# SCH_MD001_2022-09-17.net
KiCad netlist of a schematic drawn in EasyEDA
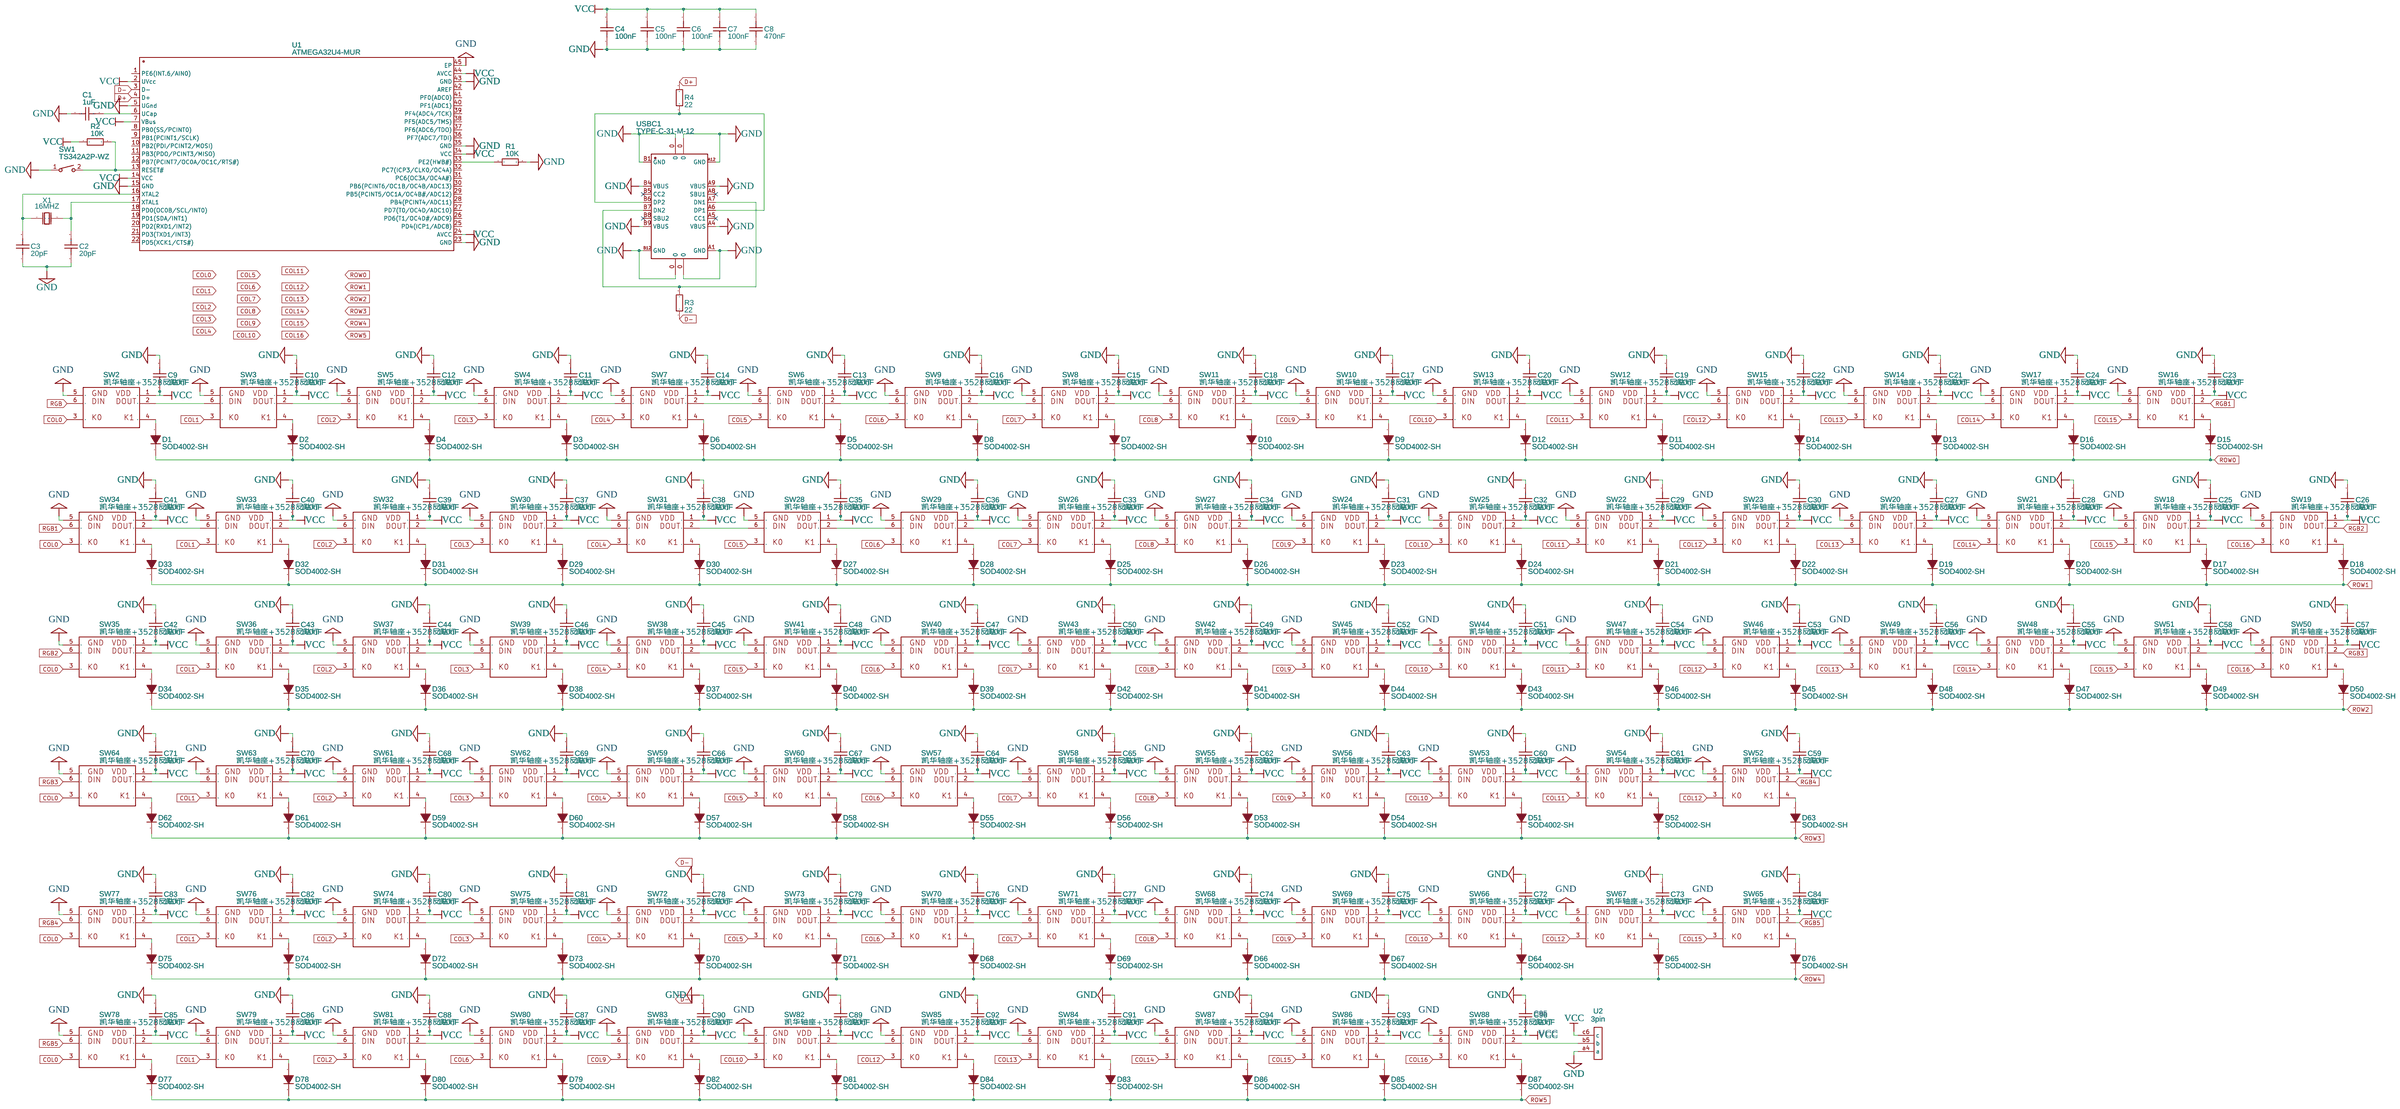
[diagram p0: schematic sheet]

(export (version "E")
  (design (tool "Eeschema 10.0.6"))
  (components
    (comp (ref "C1")
      (value "1uF")
      (fields
        (field (name "BOM_Manufacturer Part") "TCC0805X7R105K250DTS")
        (field (name "BOM_Supplier Part") "C344171")
      )
      (libsource (lib "") (part "TCC0805X7R105K250DTS"))
    )
    (comp (ref "C2")
      (value "20pF")
      (fields
        (field (name "BOM_Manufacturer Part") "VJ0805D200KXPAP")
        (field (name "BOM_Supplier Part") "C2309612")
      )
      (libsource (lib "") (part "VJ0805D200KXPAP"))
    )
    (comp (ref "C3")
      (value "20pF")
      (fields
        (field (name "BOM_Manufacturer Part") "VJ0805D200KXPAP")
        (field (name "BOM_Supplier Part") "C2309612")
      )
      (libsource (lib "") (part "VJ0805D200KXPAP"))
    )
    (comp (ref "C4")
      (value "100nF")
      (fields
        (field (name "BOM_Manufacturer Part") "VJ0805Y104MXXMG")
        (field (name "BOM_Supplier Part") "C2234470")
      )
      (libsource (lib "") (part "VJ0805Y104MXXMG"))
    )
    (comp (ref "C5")
      (value "100nF")
      (fields
        (field (name "BOM_Manufacturer Part") "VJ0805Y104MXXMG")
        (field (name "BOM_Supplier Part") "C2234470")
      )
      (libsource (lib "") (part "VJ0805Y104MXXMG"))
    )
    (comp (ref "C6")
      (value "100nF")
      (fields
        (field (name "BOM_Manufacturer Part") "VJ0805Y104MXXMG")
        (field (name "BOM_Supplier Part") "C2234470")
      )
      (libsource (lib "") (part "VJ0805Y104MXXMG"))
    )
    (comp (ref "C7")
      (value "100nF")
      (fields
        (field (name "BOM_Manufacturer Part") "VJ0805Y104MXXMG")
        (field (name "BOM_Supplier Part") "C2234470")
      )
      (libsource (lib "") (part "VJ0805Y104MXXMG"))
    )
    (comp (ref "C8")
      (value "470nF")
      (fields
        (field (name "BOM_Manufacturer Part") "TCC0805Y5V474M500DT")
        (field (name "BOM_Supplier Part") "C377012")
      )
      (libsource (lib "") (part "TCC0805Y5V474M500DT"))
    )
    (comp (ref "C9")
      (value "100nF")
      (fields
        (field (name "BOM_Manufacturer Part") "VJ0805Y104MXXMG")
        (field (name "BOM_Supplier Part") "C2234470")
      )
      (libsource (lib "") (part "VJ0805Y104MXXMG"))
    )
    (comp (ref "C10")
      (value "100nF")
      (fields
        (field (name "BOM_Manufacturer Part") "VJ0805Y104MXXMG")
        (field (name "BOM_Supplier Part") "C2234470")
      )
      (libsource (lib "") (part "VJ0805Y104MXXMG"))
    )
    (comp (ref "C11")
      (value "100nF")
      (fields
        (field (name "BOM_Manufacturer Part") "VJ0805Y104MXXMG")
        (field (name "BOM_Supplier Part") "C2234470")
      )
      (libsource (lib "") (part "VJ0805Y104MXXMG"))
    )
    (comp (ref "C12")
      (value "100nF")
      (fields
        (field (name "BOM_Manufacturer Part") "VJ0805Y104MXXMG")
        (field (name "BOM_Supplier Part") "C2234470")
      )
      (libsource (lib "") (part "VJ0805Y104MXXMG"))
    )
    (comp (ref "C13")
      (value "100nF")
      (fields
        (field (name "BOM_Manufacturer Part") "VJ0805Y104MXXMG")
        (field (name "BOM_Supplier Part") "C2234470")
      )
      (libsource (lib "") (part "VJ0805Y104MXXMG"))
    )
    (comp (ref "C14")
      (value "100nF")
      (fields
        (field (name "BOM_Manufacturer Part") "VJ0805Y104MXXMG")
        (field (name "BOM_Supplier Part") "C2234470")
      )
      (libsource (lib "") (part "VJ0805Y104MXXMG"))
    )
    (comp (ref "C15")
      (value "100nF")
      (fields
        (field (name "BOM_Manufacturer Part") "VJ0805Y104MXXMG")
        (field (name "BOM_Supplier Part") "C2234470")
      )
      (libsource (lib "") (part "VJ0805Y104MXXMG"))
    )
    (comp (ref "C16")
      (value "100nF")
      (fields
        (field (name "BOM_Manufacturer Part") "VJ0805Y104MXXMG")
        (field (name "BOM_Supplier Part") "C2234470")
      )
      (libsource (lib "") (part "VJ0805Y104MXXMG"))
    )
    (comp (ref "C17")
      (value "100nF")
      (fields
        (field (name "BOM_Manufacturer Part") "VJ0805Y104MXXMG")
        (field (name "BOM_Supplier Part") "C2234470")
      )
      (libsource (lib "") (part "VJ0805Y104MXXMG"))
    )
    (comp (ref "C18")
      (value "100nF")
      (fields
        (field (name "BOM_Manufacturer Part") "VJ0805Y104MXXMG")
        (field (name "BOM_Supplier Part") "C2234470")
      )
      (libsource (lib "") (part "VJ0805Y104MXXMG"))
    )
    (comp (ref "C19")
      (value "100nF")
      (fields
        (field (name "BOM_Manufacturer Part") "VJ0805Y104MXXMG")
        (field (name "BOM_Supplier Part") "C2234470")
      )
      (libsource (lib "") (part "VJ0805Y104MXXMG"))
    )
    (comp (ref "C20")
      (value "100nF")
      (fields
        (field (name "BOM_Manufacturer Part") "VJ0805Y104MXXMG")
        (field (name "BOM_Supplier Part") "C2234470")
      )
      (libsource (lib "") (part "VJ0805Y104MXXMG"))
    )
    (comp (ref "C21")
      (value "100nF")
      (fields
        (field (name "BOM_Manufacturer Part") "VJ0805Y104MXXMG")
        (field (name "BOM_Supplier Part") "C2234470")
      )
      (libsource (lib "") (part "VJ0805Y104MXXMG"))
    )
    (comp (ref "C22")
      (value "100nF")
      (fields
        (field (name "BOM_Manufacturer Part") "VJ0805Y104MXXMG")
        (field (name "BOM_Supplier Part") "C2234470")
      )
      (libsource (lib "") (part "VJ0805Y104MXXMG"))
    )
    (comp (ref "C23")
      (value "100nF")
      (fields
        (field (name "BOM_Manufacturer Part") "VJ0805Y104MXXMG")
        (field (name "BOM_Supplier Part") "C2234470")
      )
      (libsource (lib "") (part "VJ0805Y104MXXMG"))
    )
    (comp (ref "C24")
      (value "100nF")
      (fields
        (field (name "BOM_Manufacturer Part") "VJ0805Y104MXXMG")
        (field (name "BOM_Supplier Part") "C2234470")
      )
      (libsource (lib "") (part "VJ0805Y104MXXMG"))
    )
    (comp (ref "C25")
      (value "100nF")
      (fields
        (field (name "BOM_Manufacturer Part") "VJ0805Y104MXXMG")
        (field (name "BOM_Supplier Part") "C2234470")
      )
      (libsource (lib "") (part "VJ0805Y104MXXMG"))
    )
    (comp (ref "C26")
      (value "100nF")
      (fields
        (field (name "BOM_Manufacturer Part") "VJ0805Y104MXXMG")
        (field (name "BOM_Supplier Part") "C2234470")
      )
      (libsource (lib "") (part "VJ0805Y104MXXMG"))
    )
    (comp (ref "C27")
      (value "100nF")
      (fields
        (field (name "BOM_Manufacturer Part") "VJ0805Y104MXXMG")
        (field (name "BOM_Supplier Part") "C2234470")
      )
      (libsource (lib "") (part "VJ0805Y104MXXMG"))
    )
    (comp (ref "C28")
      (value "100nF")
      (fields
        (field (name "BOM_Manufacturer Part") "VJ0805Y104MXXMG")
        (field (name "BOM_Supplier Part") "C2234470")
      )
      (libsource (lib "") (part "VJ0805Y104MXXMG"))
    )
    (comp (ref "C29")
      (value "100nF")
      (fields
        (field (name "BOM_Manufacturer Part") "VJ0805Y104MXXMG")
        (field (name "BOM_Supplier Part") "C2234470")
      )
      (libsource (lib "") (part "VJ0805Y104MXXMG"))
    )
    (comp (ref "C30")
      (value "100nF")
      (fields
        (field (name "BOM_Manufacturer Part") "VJ0805Y104MXXMG")
        (field (name "BOM_Supplier Part") "C2234470")
      )
      (libsource (lib "") (part "VJ0805Y104MXXMG"))
    )
    (comp (ref "C31")
      (value "100nF")
      (fields
        (field (name "BOM_Manufacturer Part") "VJ0805Y104MXXMG")
        (field (name "BOM_Supplier Part") "C2234470")
      )
      (libsource (lib "") (part "VJ0805Y104MXXMG"))
    )
    (comp (ref "C32")
      (value "100nF")
      (fields
        (field (name "BOM_Manufacturer Part") "VJ0805Y104MXXMG")
        (field (name "BOM_Supplier Part") "C2234470")
      )
      (libsource (lib "") (part "VJ0805Y104MXXMG"))
    )
    (comp (ref "C33")
      (value "100nF")
      (fields
        (field (name "BOM_Manufacturer Part") "VJ0805Y104MXXMG")
        (field (name "BOM_Supplier Part") "C2234470")
      )
      (libsource (lib "") (part "VJ0805Y104MXXMG"))
    )
    (comp (ref "C34")
      (value "100nF")
      (fields
        (field (name "BOM_Manufacturer Part") "VJ0805Y104MXXMG")
        (field (name "BOM_Supplier Part") "C2234470")
      )
      (libsource (lib "") (part "VJ0805Y104MXXMG"))
    )
    (comp (ref "C35")
      (value "100nF")
      (fields
        (field (name "BOM_Manufacturer Part") "VJ0805Y104MXXMG")
        (field (name "BOM_Supplier Part") "C2234470")
      )
      (libsource (lib "") (part "VJ0805Y104MXXMG"))
    )
    (comp (ref "C36")
      (value "100nF")
      (fields
        (field (name "BOM_Manufacturer Part") "VJ0805Y104MXXMG")
        (field (name "BOM_Supplier Part") "C2234470")
      )
      (libsource (lib "") (part "VJ0805Y104MXXMG"))
    )
    (comp (ref "C37")
      (value "100nF")
      (fields
        (field (name "BOM_Manufacturer Part") "VJ0805Y104MXXMG")
        (field (name "BOM_Supplier Part") "C2234470")
      )
      (libsource (lib "") (part "VJ0805Y104MXXMG"))
    )
    (comp (ref "C38")
      (value "100nF")
      (fields
        (field (name "BOM_Manufacturer Part") "VJ0805Y104MXXMG")
        (field (name "BOM_Supplier Part") "C2234470")
      )
      (libsource (lib "") (part "VJ0805Y104MXXMG"))
    )
    (comp (ref "C39")
      (value "100nF")
      (fields
        (field (name "BOM_Manufacturer Part") "VJ0805Y104MXXMG")
        (field (name "BOM_Supplier Part") "C2234470")
      )
      (libsource (lib "") (part "VJ0805Y104MXXMG"))
    )
    (comp (ref "C40")
      (value "100nF")
      (fields
        (field (name "BOM_Manufacturer Part") "VJ0805Y104MXXMG")
        (field (name "BOM_Supplier Part") "C2234470")
      )
      (libsource (lib "") (part "VJ0805Y104MXXMG"))
    )
    (comp (ref "C41")
      (value "100nF")
      (fields
        (field (name "BOM_Manufacturer Part") "VJ0805Y104MXXMG")
        (field (name "BOM_Supplier Part") "C2234470")
      )
      (libsource (lib "") (part "VJ0805Y104MXXMG"))
    )
    (comp (ref "C42")
      (value "100nF")
      (fields
        (field (name "BOM_Manufacturer Part") "VJ0805Y104MXXMG")
        (field (name "BOM_Supplier Part") "C2234470")
      )
      (libsource (lib "") (part "VJ0805Y104MXXMG"))
    )
    (comp (ref "C43")
      (value "100nF")
      (fields
        (field (name "BOM_Manufacturer Part") "VJ0805Y104MXXMG")
        (field (name "BOM_Supplier Part") "C2234470")
      )
      (libsource (lib "") (part "VJ0805Y104MXXMG"))
    )
    (comp (ref "C44")
      (value "100nF")
      (fields
        (field (name "BOM_Manufacturer Part") "VJ0805Y104MXXMG")
        (field (name "BOM_Supplier Part") "C2234470")
      )
      (libsource (lib "") (part "VJ0805Y104MXXMG"))
    )
    (comp (ref "C45")
      (value "100nF")
      (fields
        (field (name "BOM_Manufacturer Part") "VJ0805Y104MXXMG")
        (field (name "BOM_Supplier Part") "C2234470")
      )
      (libsource (lib "") (part "VJ0805Y104MXXMG"))
    )
    (comp (ref "C46")
      (value "100nF")
      (fields
        (field (name "BOM_Manufacturer Part") "VJ0805Y104MXXMG")
        (field (name "BOM_Supplier Part") "C2234470")
      )
      (libsource (lib "") (part "VJ0805Y104MXXMG"))
    )
    (comp (ref "C47")
      (value "100nF")
      (fields
        (field (name "BOM_Manufacturer Part") "VJ0805Y104MXXMG")
        (field (name "BOM_Supplier Part") "C2234470")
      )
      (libsource (lib "") (part "VJ0805Y104MXXMG"))
    )
    (comp (ref "C48")
      (value "100nF")
      (fields
        (field (name "BOM_Manufacturer Part") "VJ0805Y104MXXMG")
        (field (name "BOM_Supplier Part") "C2234470")
      )
      (libsource (lib "") (part "VJ0805Y104MXXMG"))
    )
    (comp (ref "C49")
      (value "100nF")
      (fields
        (field (name "BOM_Manufacturer Part") "VJ0805Y104MXXMG")
        (field (name "BOM_Supplier Part") "C2234470")
      )
      (libsource (lib "") (part "VJ0805Y104MXXMG"))
    )
    (comp (ref "C50")
      (value "100nF")
      (fields
        (field (name "BOM_Manufacturer Part") "VJ0805Y104MXXMG")
        (field (name "BOM_Supplier Part") "C2234470")
      )
      (libsource (lib "") (part "VJ0805Y104MXXMG"))
    )
    (comp (ref "C51")
      (value "100nF")
      (fields
        (field (name "BOM_Manufacturer Part") "VJ0805Y104MXXMG")
        (field (name "BOM_Supplier Part") "C2234470")
      )
      (libsource (lib "") (part "VJ0805Y104MXXMG"))
    )
    (comp (ref "C52")
      (value "100nF")
      (fields
        (field (name "BOM_Manufacturer Part") "VJ0805Y104MXXMG")
        (field (name "BOM_Supplier Part") "C2234470")
      )
      (libsource (lib "") (part "VJ0805Y104MXXMG"))
    )
    (comp (ref "C53")
      (value "100nF")
      (fields
        (field (name "BOM_Manufacturer Part") "VJ0805Y104MXXMG")
        (field (name "BOM_Supplier Part") "C2234470")
      )
      (libsource (lib "") (part "VJ0805Y104MXXMG"))
    )
    (comp (ref "C54")
      (value "100nF")
      (fields
        (field (name "BOM_Manufacturer Part") "VJ0805Y104MXXMG")
        (field (name "BOM_Supplier Part") "C2234470")
      )
      (libsource (lib "") (part "VJ0805Y104MXXMG"))
    )
    (comp (ref "C55")
      (value "100nF")
      (fields
        (field (name "BOM_Manufacturer Part") "VJ0805Y104MXXMG")
        (field (name "BOM_Supplier Part") "C2234470")
      )
      (libsource (lib "") (part "VJ0805Y104MXXMG"))
    )
    (comp (ref "C56")
      (value "100nF")
      (fields
        (field (name "BOM_Manufacturer Part") "VJ0805Y104MXXMG")
        (field (name "BOM_Supplier Part") "C2234470")
      )
      (libsource (lib "") (part "VJ0805Y104MXXMG"))
    )
    (comp (ref "C57")
      (value "100nF")
      (fields
        (field (name "BOM_Manufacturer Part") "VJ0805Y104MXXMG")
        (field (name "BOM_Supplier Part") "C2234470")
      )
      (libsource (lib "") (part "VJ0805Y104MXXMG"))
    )
    (comp (ref "C58")
      (value "100nF")
      (fields
        (field (name "BOM_Manufacturer Part") "VJ0805Y104MXXMG")
        (field (name "BOM_Supplier Part") "C2234470")
      )
      (libsource (lib "") (part "VJ0805Y104MXXMG"))
    )
    (comp (ref "C59")
      (value "100nF")
      (fields
        (field (name "BOM_Manufacturer Part") "VJ0805Y104MXXMG")
        (field (name "BOM_Supplier Part") "C2234470")
      )
      (libsource (lib "") (part "VJ0805Y104MXXMG"))
    )
    (comp (ref "C60")
      (value "100nF")
      (fields
        (field (name "BOM_Manufacturer Part") "VJ0805Y104MXXMG")
        (field (name "BOM_Supplier Part") "C2234470")
      )
      (libsource (lib "") (part "VJ0805Y104MXXMG"))
    )
    (comp (ref "C61")
      (value "100nF")
      (fields
        (field (name "BOM_Manufacturer Part") "VJ0805Y104MXXMG")
        (field (name "BOM_Supplier Part") "C2234470")
      )
      (libsource (lib "") (part "VJ0805Y104MXXMG"))
    )
    (comp (ref "C62")
      (value "100nF")
      (fields
        (field (name "BOM_Manufacturer Part") "VJ0805Y104MXXMG")
        (field (name "BOM_Supplier Part") "C2234470")
      )
      (libsource (lib "") (part "VJ0805Y104MXXMG"))
    )
    (comp (ref "C63")
      (value "100nF")
      (fields
        (field (name "BOM_Manufacturer Part") "VJ0805Y104MXXMG")
        (field (name "BOM_Supplier Part") "C2234470")
      )
      (libsource (lib "") (part "VJ0805Y104MXXMG"))
    )
    (comp (ref "C64")
      (value "100nF")
      (fields
        (field (name "BOM_Manufacturer Part") "VJ0805Y104MXXMG")
        (field (name "BOM_Supplier Part") "C2234470")
      )
      (libsource (lib "") (part "VJ0805Y104MXXMG"))
    )
    (comp (ref "C65")
      (value "100nF")
      (fields
        (field (name "BOM_Manufacturer Part") "VJ0805Y104MXXMG")
        (field (name "BOM_Supplier Part") "C2234470")
      )
      (libsource (lib "") (part "VJ0805Y104MXXMG"))
    )
    (comp (ref "C66")
      (value "100nF")
      (fields
        (field (name "BOM_Manufacturer Part") "VJ0805Y104MXXMG")
        (field (name "BOM_Supplier Part") "C2234470")
      )
      (libsource (lib "") (part "VJ0805Y104MXXMG"))
    )
    (comp (ref "C67")
      (value "100nF")
      (fields
        (field (name "BOM_Manufacturer Part") "VJ0805Y104MXXMG")
        (field (name "BOM_Supplier Part") "C2234470")
      )
      (libsource (lib "") (part "VJ0805Y104MXXMG"))
    )
    (comp (ref "C68")
      (value "100nF")
      (fields
        (field (name "BOM_Manufacturer Part") "VJ0805Y104MXXMG")
        (field (name "BOM_Supplier Part") "C2234470")
      )
      (libsource (lib "") (part "VJ0805Y104MXXMG"))
    )
    (comp (ref "C69")
      (value "100nF")
      (fields
        (field (name "BOM_Manufacturer Part") "VJ0805Y104MXXMG")
        (field (name "BOM_Supplier Part") "C2234470")
      )
      (libsource (lib "") (part "VJ0805Y104MXXMG"))
    )
    (comp (ref "C70")
      (value "100nF")
      (fields
        (field (name "BOM_Manufacturer Part") "VJ0805Y104MXXMG")
        (field (name "BOM_Supplier Part") "C2234470")
      )
      (libsource (lib "") (part "VJ0805Y104MXXMG"))
    )
    (comp (ref "C71")
      (value "100nF")
      (fields
        (field (name "BOM_Manufacturer Part") "VJ0805Y104MXXMG")
        (field (name "BOM_Supplier Part") "C2234470")
      )
      (libsource (lib "") (part "VJ0805Y104MXXMG"))
    )
    (comp (ref "C72")
      (value "100nF")
      (fields
        (field (name "BOM_Manufacturer Part") "VJ0805Y104MXXMG")
        (field (name "BOM_Supplier Part") "C2234470")
      )
      (libsource (lib "") (part "VJ0805Y104MXXMG"))
    )
    (comp (ref "C73")
      (value "100nF")
      (fields
        (field (name "BOM_Manufacturer Part") "VJ0805Y104MXXMG")
        (field (name "BOM_Supplier Part") "C2234470")
      )
      (libsource (lib "") (part "VJ0805Y104MXXMG"))
    )
    (comp (ref "C74")
      (value "100nF")
      (fields
        (field (name "BOM_Manufacturer Part") "VJ0805Y104MXXMG")
        (field (name "BOM_Supplier Part") "C2234470")
      )
      (libsource (lib "") (part "VJ0805Y104MXXMG"))
    )
    (comp (ref "C75")
      (value "100nF")
      (fields
        (field (name "BOM_Manufacturer Part") "VJ0805Y104MXXMG")
        (field (name "BOM_Supplier Part") "C2234470")
      )
      (libsource (lib "") (part "VJ0805Y104MXXMG"))
    )
    (comp (ref "C76")
      (value "100nF")
      (fields
        (field (name "BOM_Manufacturer Part") "VJ0805Y104MXXMG")
        (field (name "BOM_Supplier Part") "C2234470")
      )
      (libsource (lib "") (part "VJ0805Y104MXXMG"))
    )
    (comp (ref "C77")
      (value "100nF")
      (fields
        (field (name "BOM_Manufacturer Part") "VJ0805Y104MXXMG")
        (field (name "BOM_Supplier Part") "C2234470")
      )
      (libsource (lib "") (part "VJ0805Y104MXXMG"))
    )
    (comp (ref "C78")
      (value "100nF")
      (fields
        (field (name "BOM_Manufacturer Part") "VJ0805Y104MXXMG")
        (field (name "BOM_Supplier Part") "C2234470")
      )
      (libsource (lib "") (part "VJ0805Y104MXXMG"))
    )
    (comp (ref "C79")
      (value "100nF")
      (fields
        (field (name "BOM_Manufacturer Part") "VJ0805Y104MXXMG")
        (field (name "BOM_Supplier Part") "C2234470")
      )
      (libsource (lib "") (part "VJ0805Y104MXXMG"))
    )
    (comp (ref "C80")
      (value "100nF")
      (fields
        (field (name "BOM_Manufacturer Part") "VJ0805Y104MXXMG")
        (field (name "BOM_Supplier Part") "C2234470")
      )
      (libsource (lib "") (part "VJ0805Y104MXXMG"))
    )
    (comp (ref "C81")
      (value "100nF")
      (fields
        (field (name "BOM_Manufacturer Part") "VJ0805Y104MXXMG")
        (field (name "BOM_Supplier Part") "C2234470")
      )
      (libsource (lib "") (part "VJ0805Y104MXXMG"))
    )
    (comp (ref "C82")
      (value "100nF")
      (fields
        (field (name "BOM_Manufacturer Part") "VJ0805Y104MXXMG")
        (field (name "BOM_Supplier Part") "C2234470")
      )
      (libsource (lib "") (part "VJ0805Y104MXXMG"))
    )
    (comp (ref "C83")
      (value "100nF")
      (fields
        (field (name "BOM_Manufacturer Part") "VJ0805Y104MXXMG")
        (field (name "BOM_Supplier Part") "C2234470")
      )
      (libsource (lib "") (part "VJ0805Y104MXXMG"))
    )
    (comp (ref "C84")
      (value "100nF")
      (fields
        (field (name "BOM_Manufacturer Part") "VJ0805Y104MXXMG")
        (field (name "BOM_Supplier Part") "C2234470")
      )
      (libsource (lib "") (part "VJ0805Y104MXXMG"))
    )
    (comp (ref "C85")
      (value "100nF")
      (fields
        (field (name "BOM_Manufacturer Part") "VJ0805Y104MXXMG")
        (field (name "BOM_Supplier Part") "C2234470")
      )
      (libsource (lib "") (part "VJ0805Y104MXXMG"))
    )
    (comp (ref "C86")
      (value "100nF")
      (fields
        (field (name "BOM_Manufacturer Part") "VJ0805Y104MXXMG")
        (field (name "BOM_Supplier Part") "C2234470")
      )
      (libsource (lib "") (part "VJ0805Y104MXXMG"))
    )
    (comp (ref "C87")
      (value "100nF")
      (fields
        (field (name "BOM_Manufacturer Part") "VJ0805Y104MXXMG")
        (field (name "BOM_Supplier Part") "C2234470")
      )
      (libsource (lib "") (part "VJ0805Y104MXXMG"))
    )
    (comp (ref "C88")
      (value "100nF")
      (fields
        (field (name "BOM_Manufacturer Part") "VJ0805Y104MXXMG")
        (field (name "BOM_Supplier Part") "C2234470")
      )
      (libsource (lib "") (part "VJ0805Y104MXXMG"))
    )
    (comp (ref "C89")
      (value "100nF")
      (fields
        (field (name "BOM_Manufacturer Part") "VJ0805Y104MXXMG")
        (field (name "BOM_Supplier Part") "C2234470")
      )
      (libsource (lib "") (part "VJ0805Y104MXXMG"))
    )
    (comp (ref "C90")
      (value "100nF")
      (fields
        (field (name "BOM_Manufacturer Part") "VJ0805Y104MXXMG")
        (field (name "BOM_Supplier Part") "C2234470")
      )
      (libsource (lib "") (part "VJ0805Y104MXXMG"))
    )
    (comp (ref "C91")
      (value "100nF")
      (fields
        (field (name "BOM_Manufacturer Part") "VJ0805Y104MXXMG")
        (field (name "BOM_Supplier Part") "C2234470")
      )
      (libsource (lib "") (part "VJ0805Y104MXXMG"))
    )
    (comp (ref "C92")
      (value "100nF")
      (fields
        (field (name "BOM_Manufacturer Part") "VJ0805Y104MXXMG")
        (field (name "BOM_Supplier Part") "C2234470")
      )
      (libsource (lib "") (part "VJ0805Y104MXXMG"))
    )
    (comp (ref "C93")
      (value "100nF")
      (fields
        (field (name "BOM_Manufacturer Part") "VJ0805Y104MXXMG")
        (field (name "BOM_Supplier Part") "C2234470")
      )
      (libsource (lib "") (part "VJ0805Y104MXXMG"))
    )
    (comp (ref "C94")
      (value "100nF")
      (fields
        (field (name "BOM_Manufacturer Part") "VJ0805Y104MXXMG")
        (field (name "BOM_Supplier Part") "C2234470")
      )
      (libsource (lib "") (part "VJ0805Y104MXXMG"))
    )
    (comp (ref "C96")
      (value "100nF")
      (fields
        (field (name "BOM_Manufacturer Part") "VJ0805Y104MXXMG")
        (field (name "BOM_Supplier Part") "C2234470")
      )
      (libsource (lib "") (part "VJ0805Y104MXXMG"))
    )
    (comp (ref "D1")
      (value "SOD4002-SH")
      (fields (field (name "BOM_Supplier Part") "C154996"))
      (libsource (lib "") (part "SOD4002-SH_1"))
    )
    (comp (ref "D2")
      (value "SOD4002-SH")
      (fields (field (name "BOM_Supplier Part") "C154996"))
      (libsource (lib "") (part "SOD4002-SH_1"))
    )
    (comp (ref "D3")
      (value "SOD4002-SH")
      (fields (field (name "BOM_Supplier Part") "C154996"))
      (libsource (lib "") (part "SOD4002-SH_1"))
    )
    (comp (ref "D4")
      (value "SOD4002-SH")
      (fields (field (name "BOM_Supplier Part") "C154996"))
      (libsource (lib "") (part "SOD4002-SH_1"))
    )
    (comp (ref "D5")
      (value "SOD4002-SH")
      (fields (field (name "BOM_Supplier Part") "C154996"))
      (libsource (lib "") (part "SOD4002-SH_1"))
    )
    (comp (ref "D6")
      (value "SOD4002-SH")
      (fields (field (name "BOM_Supplier Part") "C154996"))
      (libsource (lib "") (part "SOD4002-SH_1"))
    )
    (comp (ref "D7")
      (value "SOD4002-SH")
      (fields (field (name "BOM_Supplier Part") "C154996"))
      (libsource (lib "") (part "SOD4002-SH_1"))
    )
    (comp (ref "D8")
      (value "SOD4002-SH")
      (fields (field (name "BOM_Supplier Part") "C154996"))
      (libsource (lib "") (part "SOD4002-SH_1"))
    )
    (comp (ref "D9")
      (value "SOD4002-SH")
      (fields (field (name "BOM_Supplier Part") "C154996"))
      (libsource (lib "") (part "SOD4002-SH_1"))
    )
    (comp (ref "D10")
      (value "SOD4002-SH")
      (fields (field (name "BOM_Supplier Part") "C154996"))
      (libsource (lib "") (part "SOD4002-SH_1"))
    )
    (comp (ref "D11")
      (value "SOD4002-SH")
      (fields (field (name "BOM_Supplier Part") "C154996"))
      (libsource (lib "") (part "SOD4002-SH_1"))
    )
    (comp (ref "D12")
      (value "SOD4002-SH")
      (fields (field (name "BOM_Supplier Part") "C154996"))
      (libsource (lib "") (part "SOD4002-SH_1"))
    )
    (comp (ref "D13")
      (value "SOD4002-SH")
      (fields (field (name "BOM_Supplier Part") "C154996"))
      (libsource (lib "") (part "SOD4002-SH_1"))
    )
    (comp (ref "D14")
      (value "SOD4002-SH")
      (fields (field (name "BOM_Supplier Part") "C154996"))
      (libsource (lib "") (part "SOD4002-SH_1"))
    )
    (comp (ref "D15")
      (value "SOD4002-SH")
      (fields (field (name "BOM_Supplier Part") "C154996"))
      (libsource (lib "") (part "SOD4002-SH_1"))
    )
    (comp (ref "D16")
      (value "SOD4002-SH")
      (fields (field (name "BOM_Supplier Part") "C154996"))
      (libsource (lib "") (part "SOD4002-SH_1"))
    )
    (comp (ref "D17")
      (value "SOD4002-SH")
      (fields (field (name "BOM_Supplier Part") "C154996"))
      (libsource (lib "") (part "SOD4002-SH"))
    )
    (comp (ref "D18")
      (value "SOD4002-SH")
      (fields (field (name "BOM_Supplier Part") "C154996"))
      (libsource (lib "") (part "SOD4002-SH"))
    )
    (comp (ref "D19")
      (value "SOD4002-SH")
      (fields (field (name "BOM_Supplier Part") "C154996"))
      (libsource (lib "") (part "SOD4002-SH"))
    )
    (comp (ref "D20")
      (value "SOD4002-SH")
      (fields (field (name "BOM_Supplier Part") "C154996"))
      (libsource (lib "") (part "SOD4002-SH"))
    )
    (comp (ref "D21")
      (value "SOD4002-SH")
      (fields (field (name "BOM_Supplier Part") "C154996"))
      (libsource (lib "") (part "SOD4002-SH"))
    )
    (comp (ref "D22")
      (value "SOD4002-SH")
      (fields (field (name "BOM_Supplier Part") "C154996"))
      (libsource (lib "") (part "SOD4002-SH"))
    )
    (comp (ref "D23")
      (value "SOD4002-SH")
      (fields (field (name "BOM_Supplier Part") "C154996"))
      (libsource (lib "") (part "SOD4002-SH"))
    )
    (comp (ref "D24")
      (value "SOD4002-SH")
      (fields (field (name "BOM_Supplier Part") "C154996"))
      (libsource (lib "") (part "SOD4002-SH"))
    )
    (comp (ref "D25")
      (value "SOD4002-SH")
      (fields (field (name "BOM_Supplier Part") "C154996"))
      (libsource (lib "") (part "SOD4002-SH"))
    )
    (comp (ref "D26")
      (value "SOD4002-SH")
      (fields (field (name "BOM_Supplier Part") "C154996"))
      (libsource (lib "") (part "SOD4002-SH"))
    )
    (comp (ref "D27")
      (value "SOD4002-SH")
      (fields (field (name "BOM_Supplier Part") "C154996"))
      (libsource (lib "") (part "SOD4002-SH"))
    )
    (comp (ref "D28")
      (value "SOD4002-SH")
      (fields (field (name "BOM_Supplier Part") "C154996"))
      (libsource (lib "") (part "SOD4002-SH"))
    )
    (comp (ref "D29")
      (value "SOD4002-SH")
      (fields (field (name "BOM_Supplier Part") "C154996"))
      (libsource (lib "") (part "SOD4002-SH"))
    )
    (comp (ref "D30")
      (value "SOD4002-SH")
      (fields (field (name "BOM_Supplier Part") "C154996"))
      (libsource (lib "") (part "SOD4002-SH"))
    )
    (comp (ref "D31")
      (value "SOD4002-SH")
      (fields (field (name "BOM_Supplier Part") "C154996"))
      (libsource (lib "") (part "SOD4002-SH"))
    )
    (comp (ref "D32")
      (value "SOD4002-SH")
      (fields (field (name "BOM_Supplier Part") "C154996"))
      (libsource (lib "") (part "SOD4002-SH"))
    )
    (comp (ref "D33")
      (value "SOD4002-SH")
      (fields (field (name "BOM_Supplier Part") "C154996"))
      (libsource (lib "") (part "SOD4002-SH"))
    )
    (comp (ref "D34")
      (value "SOD4002-SH")
      (fields (field (name "BOM_Supplier Part") "C154996"))
      (libsource (lib "") (part "SOD4002-SH"))
    )
    (comp (ref "D35")
      (value "SOD4002-SH")
      (fields (field (name "BOM_Supplier Part") "C154996"))
      (libsource (lib "") (part "SOD4002-SH"))
    )
    (comp (ref "D36")
      (value "SOD4002-SH")
      (fields (field (name "BOM_Supplier Part") "C154996"))
      (libsource (lib "") (part "SOD4002-SH"))
    )
    (comp (ref "D37")
      (value "SOD4002-SH")
      (fields (field (name "BOM_Supplier Part") "C154996"))
      (libsource (lib "") (part "SOD4002-SH"))
    )
    (comp (ref "D38")
      (value "SOD4002-SH")
      (fields (field (name "BOM_Supplier Part") "C154996"))
      (libsource (lib "") (part "SOD4002-SH"))
    )
    (comp (ref "D39")
      (value "SOD4002-SH")
      (fields (field (name "BOM_Supplier Part") "C154996"))
      (libsource (lib "") (part "SOD4002-SH"))
    )
    (comp (ref "D40")
      (value "SOD4002-SH")
      (fields (field (name "BOM_Supplier Part") "C154996"))
      (libsource (lib "") (part "SOD4002-SH"))
    )
    (comp (ref "D41")
      (value "SOD4002-SH")
      (fields (field (name "BOM_Supplier Part") "C154996"))
      (libsource (lib "") (part "SOD4002-SH"))
    )
    (comp (ref "D42")
      (value "SOD4002-SH")
      (fields (field (name "BOM_Supplier Part") "C154996"))
      (libsource (lib "") (part "SOD4002-SH"))
    )
    (comp (ref "D43")
      (value "SOD4002-SH")
      (fields (field (name "BOM_Supplier Part") "C154996"))
      (libsource (lib "") (part "SOD4002-SH"))
    )
    (comp (ref "D44")
      (value "SOD4002-SH")
      (fields (field (name "BOM_Supplier Part") "C154996"))
      (libsource (lib "") (part "SOD4002-SH"))
    )
    (comp (ref "D45")
      (value "SOD4002-SH")
      (fields (field (name "BOM_Supplier Part") "C154996"))
      (libsource (lib "") (part "SOD4002-SH"))
    )
    (comp (ref "D46")
      (value "SOD4002-SH")
      (fields (field (name "BOM_Supplier Part") "C154996"))
      (libsource (lib "") (part "SOD4002-SH"))
    )
    (comp (ref "D47")
      (value "SOD4002-SH")
      (fields (field (name "BOM_Supplier Part") "C154996"))
      (libsource (lib "") (part "SOD4002-SH"))
    )
    (comp (ref "D48")
      (value "SOD4002-SH")
      (fields (field (name "BOM_Supplier Part") "C154996"))
      (libsource (lib "") (part "SOD4002-SH"))
    )
    (comp (ref "D49")
      (value "SOD4002-SH")
      (fields (field (name "BOM_Supplier Part") "C154996"))
      (libsource (lib "") (part "SOD4002-SH"))
    )
    (comp (ref "D50")
      (value "SOD4002-SH")
      (fields (field (name "BOM_Supplier Part") "C154996"))
      (libsource (lib "") (part "SOD4002-SH"))
    )
    (comp (ref "D51")
      (value "SOD4002-SH")
      (fields (field (name "BOM_Supplier Part") "C154996"))
      (libsource (lib "") (part "SOD4002-SH"))
    )
    (comp (ref "D52")
      (value "SOD4002-SH")
      (fields (field (name "BOM_Supplier Part") "C154996"))
      (libsource (lib "") (part "SOD4002-SH"))
    )
    (comp (ref "D53")
      (value "SOD4002-SH")
      (fields (field (name "BOM_Supplier Part") "C154996"))
      (libsource (lib "") (part "SOD4002-SH"))
    )
    (comp (ref "D54")
      (value "SOD4002-SH")
      (fields (field (name "BOM_Supplier Part") "C154996"))
      (libsource (lib "") (part "SOD4002-SH"))
    )
    (comp (ref "D55")
      (value "SOD4002-SH")
      (fields (field (name "BOM_Supplier Part") "C154996"))
      (libsource (lib "") (part "SOD4002-SH"))
    )
    (comp (ref "D56")
      (value "SOD4002-SH")
      (fields (field (name "BOM_Supplier Part") "C154996"))
      (libsource (lib "") (part "SOD4002-SH"))
    )
    (comp (ref "D57")
      (value "SOD4002-SH")
      (fields (field (name "BOM_Supplier Part") "C154996"))
      (libsource (lib "") (part "SOD4002-SH"))
    )
    (comp (ref "D58")
      (value "SOD4002-SH")
      (fields (field (name "BOM_Supplier Part") "C154996"))
      (libsource (lib "") (part "SOD4002-SH"))
    )
    (comp (ref "D59")
      (value "SOD4002-SH")
      (fields (field (name "BOM_Supplier Part") "C154996"))
      (libsource (lib "") (part "SOD4002-SH"))
    )
    (comp (ref "D60")
      (value "SOD4002-SH")
      (fields (field (name "BOM_Supplier Part") "C154996"))
      (libsource (lib "") (part "SOD4002-SH"))
    )
    (comp (ref "D61")
      (value "SOD4002-SH")
      (fields (field (name "BOM_Supplier Part") "C154996"))
      (libsource (lib "") (part "SOD4002-SH"))
    )
    (comp (ref "D62")
      (value "SOD4002-SH")
      (fields (field (name "BOM_Supplier Part") "C154996"))
      (libsource (lib "") (part "SOD4002-SH"))
    )
    (comp (ref "D63")
      (value "SOD4002-SH")
      (fields (field (name "BOM_Supplier Part") "C154996"))
      (libsource (lib "") (part "SOD4002-SH"))
    )
    (comp (ref "D64")
      (value "SOD4002-SH")
      (fields (field (name "BOM_Supplier Part") "C154996"))
      (libsource (lib "") (part "SOD4002-SH"))
    )
    (comp (ref "D65")
      (value "SOD4002-SH")
      (fields (field (name "BOM_Supplier Part") "C154996"))
      (libsource (lib "") (part "SOD4002-SH"))
    )
    (comp (ref "D66")
      (value "SOD4002-SH")
      (fields (field (name "BOM_Supplier Part") "C154996"))
      (libsource (lib "") (part "SOD4002-SH"))
    )
    (comp (ref "D67")
      (value "SOD4002-SH")
      (fields (field (name "BOM_Supplier Part") "C154996"))
      (libsource (lib "") (part "SOD4002-SH"))
    )
    (comp (ref "D68")
      (value "SOD4002-SH")
      (fields (field (name "BOM_Supplier Part") "C154996"))
      (libsource (lib "") (part "SOD4002-SH"))
    )
    (comp (ref "D69")
      (value "SOD4002-SH")
      (fields (field (name "BOM_Supplier Part") "C154996"))
      (libsource (lib "") (part "SOD4002-SH"))
    )
    (comp (ref "D70")
      (value "SOD4002-SH")
      (fields (field (name "BOM_Supplier Part") "C154996"))
      (libsource (lib "") (part "SOD4002-SH"))
    )
    (comp (ref "D71")
      (value "SOD4002-SH")
      (fields (field (name "BOM_Supplier Part") "C154996"))
      (libsource (lib "") (part "SOD4002-SH"))
    )
    (comp (ref "D72")
      (value "SOD4002-SH")
      (fields (field (name "BOM_Supplier Part") "C154996"))
      (libsource (lib "") (part "SOD4002-SH"))
    )
    (comp (ref "D73")
      (value "SOD4002-SH")
      (fields (field (name "BOM_Supplier Part") "C154996"))
      (libsource (lib "") (part "SOD4002-SH"))
    )
    (comp (ref "D74")
      (value "SOD4002-SH")
      (fields (field (name "BOM_Supplier Part") "C154996"))
      (libsource (lib "") (part "SOD4002-SH"))
    )
    (comp (ref "D75")
      (value "SOD4002-SH")
      (fields (field (name "BOM_Supplier Part") "C154996"))
      (libsource (lib "") (part "SOD4002-SH"))
    )
    (comp (ref "D76")
      (value "SOD4002-SH")
      (fields (field (name "BOM_Supplier Part") "C154996"))
      (libsource (lib "") (part "SOD4002-SH"))
    )
    (comp (ref "D77")
      (value "SOD4002-SH")
      (fields (field (name "BOM_Supplier Part") "C154996"))
      (libsource (lib "") (part "SOD4002-SH"))
    )
    (comp (ref "D78")
      (value "SOD4002-SH")
      (fields (field (name "BOM_Supplier Part") "C154996"))
      (libsource (lib "") (part "SOD4002-SH"))
    )
    (comp (ref "D79")
      (value "SOD4002-SH")
      (fields (field (name "BOM_Supplier Part") "C154996"))
      (libsource (lib "") (part "SOD4002-SH"))
    )
    (comp (ref "D80")
      (value "SOD4002-SH")
      (fields (field (name "BOM_Supplier Part") "C154996"))
      (libsource (lib "") (part "SOD4002-SH"))
    )
    (comp (ref "D81")
      (value "SOD4002-SH")
      (fields (field (name "BOM_Supplier Part") "C154996"))
      (libsource (lib "") (part "SOD4002-SH"))
    )
    (comp (ref "D82")
      (value "SOD4002-SH")
      (fields (field (name "BOM_Supplier Part") "C154996"))
      (libsource (lib "") (part "SOD4002-SH"))
    )
    (comp (ref "D83")
      (value "SOD4002-SH")
      (fields (field (name "BOM_Supplier Part") "C154996"))
      (libsource (lib "") (part "SOD4002-SH"))
    )
    (comp (ref "D84")
      (value "SOD4002-SH")
      (fields (field (name "BOM_Supplier Part") "C154996"))
      (libsource (lib "") (part "SOD4002-SH"))
    )
    (comp (ref "D85")
      (value "SOD4002-SH")
      (fields (field (name "BOM_Supplier Part") "C154996"))
      (libsource (lib "") (part "SOD4002-SH"))
    )
    (comp (ref "D86")
      (value "SOD4002-SH")
      (fields (field (name "BOM_Supplier Part") "C154996"))
      (libsource (lib "") (part "SOD4002-SH"))
    )
    (comp (ref "D87")
      (value "SOD4002-SH")
      (fields (field (name "BOM_Supplier Part") "C154996"))
      (libsource (lib "") (part "SOD4002-SH"))
    )
    (comp (ref "R1")
      (value "10K")
      (fields
        (field (name "BOM_Manufacturer Part") "RT0805BRD0710KL")
        (field (name "BOM_Supplier Part") "C110775")
      )
      (libsource (lib "") (part "RT0805BRD0710KL"))
    )
    (comp (ref "R2")
      (value "10K")
      (fields
        (field (name "BOM_Manufacturer Part") "RT0805BRD0710KL")
        (field (name "BOM_Supplier Part") "C110775")
      )
      (libsource (lib "") (part "RT0805BRD0710KL"))
    )
    (comp (ref "R3")
      (value "22")
      (fields
        (field (name "BOM_Manufacturer Part") "AC0805FR-0722RL")
        (field (name "BOM_Supplier Part") "C144573")
      )
      (libsource (lib "") (part "AC0805FR-0722RL"))
    )
    (comp (ref "R4")
      (value "22")
      (fields
        (field (name "BOM_Manufacturer Part") "AC0805FR-0722RL")
        (field (name "BOM_Supplier Part") "C144573")
      )
      (libsource (lib "") (part "AC0805FR-0722RL"))
    )
    (comp (ref "SW1")
      (value "TS342A2P-WZ")
      (fields (field (name "BOM_Supplier Part") "C557591"))
      (libsource (lib "") (part "TS342A2P-WZ"))
    )
    (comp (ref "SW2") (value "凯华轴座+3528反贴灯") (libsource (lib "") (part "凯华轴座+3528反贴灯")))
    (comp (ref "SW3") (value "凯华轴座+3528反贴灯") (libsource (lib "") (part "凯华轴座+3528反贴灯")))
    (comp (ref "SW4") (value "凯华轴座+3528反贴灯") (libsource (lib "") (part "凯华轴座+3528反贴灯")))
    (comp (ref "SW5") (value "凯华轴座+3528反贴灯") (libsource (lib "") (part "凯华轴座+3528反贴灯")))
    (comp (ref "SW6") (value "凯华轴座+3528反贴灯") (libsource (lib "") (part "凯华轴座+3528反贴灯")))
    (comp (ref "SW7") (value "凯华轴座+3528反贴灯") (libsource (lib "") (part "凯华轴座+3528反贴灯")))
    (comp (ref "SW8") (value "凯华轴座+3528反贴灯") (libsource (lib "") (part "凯华轴座+3528反贴灯")))
    (comp (ref "SW9") (value "凯华轴座+3528反贴灯") (libsource (lib "") (part "凯华轴座+3528反贴灯")))
    (comp (ref "SW10") (value "凯华轴座+3528反贴灯") (libsource (lib "") (part "凯华轴座+3528反贴灯")))
    (comp (ref "SW11") (value "凯华轴座+3528反贴灯") (libsource (lib "") (part "凯华轴座+3528反贴灯")))
    (comp (ref "SW12") (value "凯华轴座+3528反贴灯") (libsource (lib "") (part "凯华轴座+3528反贴灯")))
    (comp (ref "SW13") (value "凯华轴座+3528反贴灯") (libsource (lib "") (part "凯华轴座+3528反贴灯")))
    (comp (ref "SW14") (value "凯华轴座+3528反贴灯") (libsource (lib "") (part "凯华轴座+3528反贴灯")))
    (comp (ref "SW15") (value "凯华轴座+3528反贴灯") (libsource (lib "") (part "凯华轴座+3528反贴灯")))
    (comp (ref "SW16") (value "凯华轴座+3528反贴灯") (libsource (lib "") (part "凯华轴座+3528反贴灯")))
    (comp (ref "SW17") (value "凯华轴座+3528反贴灯") (libsource (lib "") (part "凯华轴座+3528反贴灯")))
    (comp (ref "SW18") (value "凯华轴座+3528反贴灯") (libsource (lib "") (part "凯华轴座+3528反贴灯")))
    (comp (ref "SW19") (value "凯华轴座+3528反贴灯") (libsource (lib "") (part "凯华轴座+3528反贴灯")))
    (comp (ref "SW20") (value "凯华轴座+3528反贴灯") (libsource (lib "") (part "凯华轴座+3528反贴灯")))
    (comp (ref "SW21") (value "凯华轴座+3528反贴灯") (libsource (lib "") (part "凯华轴座+3528反贴灯")))
    (comp (ref "SW22") (value "凯华轴座+3528反贴灯") (libsource (lib "") (part "凯华轴座+3528反贴灯")))
    (comp (ref "SW23") (value "凯华轴座+3528反贴灯") (libsource (lib "") (part "凯华轴座+3528反贴灯")))
    (comp (ref "SW24") (value "凯华轴座+3528反贴灯") (libsource (lib "") (part "凯华轴座+3528反贴灯")))
    (comp (ref "SW25") (value "凯华轴座+3528反贴灯") (libsource (lib "") (part "凯华轴座+3528反贴灯")))
    (comp (ref "SW26") (value "凯华轴座+3528反贴灯") (libsource (lib "") (part "凯华轴座+3528反贴灯")))
    (comp (ref "SW27") (value "凯华轴座+3528反贴灯") (libsource (lib "") (part "凯华轴座+3528反贴灯")))
    (comp (ref "SW28") (value "凯华轴座+3528反贴灯") (libsource (lib "") (part "凯华轴座+3528反贴灯")))
    (comp (ref "SW29") (value "凯华轴座+3528反贴灯") (libsource (lib "") (part "凯华轴座+3528反贴灯")))
    (comp (ref "SW30") (value "凯华轴座+3528反贴灯") (libsource (lib "") (part "凯华轴座+3528反贴灯")))
    (comp (ref "SW31") (value "凯华轴座+3528反贴灯") (libsource (lib "") (part "凯华轴座+3528反贴灯")))
    (comp (ref "SW32") (value "凯华轴座+3528反贴灯") (libsource (lib "") (part "凯华轴座+3528反贴灯")))
    (comp (ref "SW33") (value "凯华轴座+3528反贴灯") (libsource (lib "") (part "凯华轴座+3528反贴灯")))
    (comp (ref "SW34") (value "凯华轴座+3528反贴灯") (libsource (lib "") (part "凯华轴座+3528反贴灯")))
    (comp (ref "SW35") (value "凯华轴座+3528反贴灯") (libsource (lib "") (part "凯华轴座+3528反贴灯")))
    (comp (ref "SW36") (value "凯华轴座+3528反贴灯") (libsource (lib "") (part "凯华轴座+3528反贴灯")))
    (comp (ref "SW37") (value "凯华轴座+3528反贴灯") (libsource (lib "") (part "凯华轴座+3528反贴灯")))
    (comp (ref "SW38") (value "凯华轴座+3528反贴灯") (libsource (lib "") (part "凯华轴座+3528反贴灯")))
    (comp (ref "SW39") (value "凯华轴座+3528反贴灯") (libsource (lib "") (part "凯华轴座+3528反贴灯")))
    (comp (ref "SW40") (value "凯华轴座+3528反贴灯") (libsource (lib "") (part "凯华轴座+3528反贴灯")))
    (comp (ref "SW41") (value "凯华轴座+3528反贴灯") (libsource (lib "") (part "凯华轴座+3528反贴灯")))
    (comp (ref "SW42") (value "凯华轴座+3528反贴灯") (libsource (lib "") (part "凯华轴座+3528反贴灯")))
    (comp (ref "SW43") (value "凯华轴座+3528反贴灯") (libsource (lib "") (part "凯华轴座+3528反贴灯")))
    (comp (ref "SW44") (value "凯华轴座+3528反贴灯") (libsource (lib "") (part "凯华轴座+3528反贴灯")))
    (comp (ref "SW45") (value "凯华轴座+3528反贴灯") (libsource (lib "") (part "凯华轴座+3528反贴灯")))
    (comp (ref "SW46") (value "凯华轴座+3528反贴灯") (libsource (lib "") (part "凯华轴座+3528反贴灯")))
    (comp (ref "SW47") (value "凯华轴座+3528反贴灯") (libsource (lib "") (part "凯华轴座+3528反贴灯")))
    (comp (ref "SW48") (value "凯华轴座+3528反贴灯") (libsource (lib "") (part "凯华轴座+3528反贴灯")))
    (comp (ref "SW49") (value "凯华轴座+3528反贴灯") (libsource (lib "") (part "凯华轴座+3528反贴灯")))
    (comp (ref "SW50") (value "凯华轴座+3528反贴灯") (libsource (lib "") (part "凯华轴座+3528反贴灯")))
    (comp (ref "SW51") (value "凯华轴座+3528反贴灯") (libsource (lib "") (part "凯华轴座+3528反贴灯")))
    (comp (ref "SW52") (value "凯华轴座+3528反贴灯") (libsource (lib "") (part "凯华轴座+3528反贴灯")))
    (comp (ref "SW53") (value "凯华轴座+3528反贴灯") (libsource (lib "") (part "凯华轴座+3528反贴灯")))
    (comp (ref "SW54") (value "凯华轴座+3528反贴灯") (libsource (lib "") (part "凯华轴座+3528反贴灯")))
    (comp (ref "SW55") (value "凯华轴座+3528反贴灯") (libsource (lib "") (part "凯华轴座+3528反贴灯")))
    (comp (ref "SW56") (value "凯华轴座+3528反贴灯") (libsource (lib "") (part "凯华轴座+3528反贴灯")))
    (comp (ref "SW57") (value "凯华轴座+3528反贴灯") (libsource (lib "") (part "凯华轴座+3528反贴灯")))
    (comp (ref "SW58") (value "凯华轴座+3528反贴灯") (libsource (lib "") (part "凯华轴座+3528反贴灯")))
    (comp (ref "SW59") (value "凯华轴座+3528反贴灯") (libsource (lib "") (part "凯华轴座+3528反贴灯")))
    (comp (ref "SW60") (value "凯华轴座+3528反贴灯") (libsource (lib "") (part "凯华轴座+3528反贴灯")))
    (comp (ref "SW61") (value "凯华轴座+3528反贴灯") (libsource (lib "") (part "凯华轴座+3528反贴灯")))
    (comp (ref "SW62") (value "凯华轴座+3528反贴灯") (libsource (lib "") (part "凯华轴座+3528反贴灯")))
    (comp (ref "SW63") (value "凯华轴座+3528反贴灯") (libsource (lib "") (part "凯华轴座+3528反贴灯")))
    (comp (ref "SW64") (value "凯华轴座+3528反贴灯") (libsource (lib "") (part "凯华轴座+3528反贴灯")))
    (comp (ref "SW65") (value "凯华轴座+3528反贴灯") (libsource (lib "") (part "凯华轴座+3528反贴灯")))
    (comp (ref "SW66") (value "凯华轴座+3528反贴灯") (libsource (lib "") (part "凯华轴座+3528反贴灯")))
    (comp (ref "SW67") (value "凯华轴座+3528反贴灯") (libsource (lib "") (part "凯华轴座+3528反贴灯")))
    (comp (ref "SW68") (value "凯华轴座+3528反贴灯") (libsource (lib "") (part "凯华轴座+3528反贴灯")))
    (comp (ref "SW69") (value "凯华轴座+3528反贴灯") (libsource (lib "") (part "凯华轴座+3528反贴灯")))
    (comp (ref "SW70") (value "凯华轴座+3528反贴灯") (libsource (lib "") (part "凯华轴座+3528反贴灯")))
    (comp (ref "SW71") (value "凯华轴座+3528反贴灯") (libsource (lib "") (part "凯华轴座+3528反贴灯")))
    (comp (ref "SW72") (value "凯华轴座+3528反贴灯") (libsource (lib "") (part "凯华轴座+3528反贴灯")))
    (comp (ref "SW73") (value "凯华轴座+3528反贴灯") (libsource (lib "") (part "凯华轴座+3528反贴灯")))
    (comp (ref "SW74") (value "凯华轴座+3528反贴灯") (libsource (lib "") (part "凯华轴座+3528反贴灯")))
    (comp (ref "SW75") (value "凯华轴座+3528反贴灯") (libsource (lib "") (part "凯华轴座+3528反贴灯")))
    (comp (ref "SW76") (value "凯华轴座+3528反贴灯") (libsource (lib "") (part "凯华轴座+3528反贴灯")))
    (comp (ref "SW77") (value "凯华轴座+3528反贴灯") (libsource (lib "") (part "凯华轴座+3528反贴灯")))
    (comp (ref "SW78") (value "凯华轴座+3528反贴灯") (libsource (lib "") (part "凯华轴座+3528反贴灯")))
    (comp (ref "SW79") (value "凯华轴座+3528反贴灯") (libsource (lib "") (part "凯华轴座+3528反贴灯")))
    (comp (ref "SW80") (value "凯华轴座+3528反贴灯") (libsource (lib "") (part "凯华轴座+3528反贴灯")))
    (comp (ref "SW81") (value "凯华轴座+3528反贴灯") (libsource (lib "") (part "凯华轴座+3528反贴灯")))
    (comp (ref "SW82") (value "凯华轴座+3528反贴灯") (libsource (lib "") (part "凯华轴座+3528反贴灯")))
    (comp (ref "SW83") (value "凯华轴座+3528反贴灯") (libsource (lib "") (part "凯华轴座+3528反贴灯")))
    (comp (ref "SW84") (value "凯华轴座+3528反贴灯") (libsource (lib "") (part "凯华轴座+3528反贴灯")))
    (comp (ref "SW85") (value "凯华轴座+3528反贴灯") (libsource (lib "") (part "凯华轴座+3528反贴灯")))
    (comp (ref "SW86") (value "凯华轴座+3528反贴灯") (libsource (lib "") (part "凯华轴座+3528反贴灯")))
    (comp (ref "SW87") (value "凯华轴座+3528反贴灯") (libsource (lib "") (part "凯华轴座+3528反贴灯")))
    (comp (ref "SW88") (value "凯华轴座+3528反贴灯") (libsource (lib "") (part "凯华轴座+3528反贴灯")))
    (comp (ref "U1")
      (value "ATMEGA32U4-MUR")
      (fields (field (name "BOM_Supplier Part") "C45874"))
      (libsource (lib "") (part "ATMEGA32U4-MUR"))
    )
    (comp (ref "U2") (value "3pin") (libsource (lib "") (part "3pin")))
    (comp (ref "USBC1")
      (value "TYPE-C-31-M-12")
      (fields (field (name "BOM_Supplier Part") "C165948"))
      (libsource (lib "") (part "TYPE-C-31-M-12"))
    )
    (comp (ref "X1")
      (value "16MHZ")
      (fields
        (field (name "BOM_Manufacturer Part") "XSHEELNANF-16MHZ")
        (field (name "BOM_Supplier Part") "C242221")
      )
      (libsource (lib "") (part "XSHEELNANF-16MHZ"))
    )
  )
  (nets
    (net (code "1") (name "COL0") (class "Default")
      (node (ref "SW2") (pin "3") (pinfunction "3_3") (pintype "unspecified"))
      (node (ref "SW34") (pin "3") (pinfunction "3_3") (pintype "unspecified"))
      (node (ref "SW35") (pin "3") (pinfunction "3_3") (pintype "unspecified"))
      (node (ref "SW64") (pin "3") (pinfunction "3_3") (pintype "unspecified"))
      (node (ref "SW77") (pin "3") (pinfunction "3_3") (pintype "unspecified"))
      (node (ref "SW78") (pin "3") (pinfunction "3_3") (pintype "unspecified"))
    )
    (net (code "2") (name "COL1") (class "Default")
      (node (ref "SW3") (pin "3") (pinfunction "3_3") (pintype "unspecified"))
      (node (ref "SW33") (pin "3") (pinfunction "3_3") (pintype "unspecified"))
      (node (ref "SW36") (pin "3") (pinfunction "3_3") (pintype "unspecified"))
      (node (ref "SW63") (pin "3") (pinfunction "3_3") (pintype "unspecified"))
      (node (ref "SW76") (pin "3") (pinfunction "3_3") (pintype "unspecified"))
      (node (ref "SW79") (pin "3") (pinfunction "3_3") (pintype "unspecified"))
    )
    (net (code "3") (name "COL2") (class "Default")
      (node (ref "SW32") (pin "3") (pinfunction "3_3") (pintype "unspecified"))
      (node (ref "SW37") (pin "3") (pinfunction "3_3") (pintype "unspecified"))
      (node (ref "SW5") (pin "3") (pinfunction "3_3") (pintype "unspecified"))
      (node (ref "SW61") (pin "3") (pinfunction "3_3") (pintype "unspecified"))
      (node (ref "SW74") (pin "3") (pinfunction "3_3") (pintype "unspecified"))
      (node (ref "SW81") (pin "3") (pinfunction "3_3") (pintype "unspecified"))
    )
    (net (code "4") (name "COL3") (class "Default")
      (node (ref "SW30") (pin "3") (pinfunction "3_3") (pintype "unspecified"))
      (node (ref "SW39") (pin "3") (pinfunction "3_3") (pintype "unspecified"))
      (node (ref "SW4") (pin "3") (pinfunction "3_3") (pintype "unspecified"))
      (node (ref "SW62") (pin "3") (pinfunction "3_3") (pintype "unspecified"))
      (node (ref "SW75") (pin "3") (pinfunction "3_3") (pintype "unspecified"))
    )
    (net (code "5") (name "COL4") (class "Default")
      (node (ref "SW31") (pin "3") (pinfunction "3_3") (pintype "unspecified"))
      (node (ref "SW38") (pin "3") (pinfunction "3_3") (pintype "unspecified"))
      (node (ref "SW59") (pin "3") (pinfunction "3_3") (pintype "unspecified"))
      (node (ref "SW7") (pin "3") (pinfunction "3_3") (pintype "unspecified"))
      (node (ref "SW72") (pin "3") (pinfunction "3_3") (pintype "unspecified"))
    )
    (net (code "6") (name "COL5") (class "Default")
      (node (ref "SW28") (pin "3") (pinfunction "3_3") (pintype "unspecified"))
      (node (ref "SW41") (pin "3") (pinfunction "3_3") (pintype "unspecified"))
      (node (ref "SW6") (pin "3") (pinfunction "3_3") (pintype "unspecified"))
      (node (ref "SW60") (pin "3") (pinfunction "3_3") (pintype "unspecified"))
      (node (ref "SW73") (pin "3") (pinfunction "3_3") (pintype "unspecified"))
    )
    (net (code "7") (name "COL6") (class "Default")
      (node (ref "SW29") (pin "3") (pinfunction "3_3") (pintype "unspecified"))
      (node (ref "SW40") (pin "3") (pinfunction "3_3") (pintype "unspecified"))
      (node (ref "SW57") (pin "3") (pinfunction "3_3") (pintype "unspecified"))
      (node (ref "SW70") (pin "3") (pinfunction "3_3") (pintype "unspecified"))
      (node (ref "SW80") (pin "3") (pinfunction "3_3") (pintype "unspecified"))
      (node (ref "SW9") (pin "3") (pinfunction "3_3") (pintype "unspecified"))
    )
    (net (code "8") (name "COL7") (class "Default")
      (node (ref "SW26") (pin "3") (pinfunction "3_3") (pintype "unspecified"))
      (node (ref "SW43") (pin "3") (pinfunction "3_3") (pintype "unspecified"))
      (node (ref "SW58") (pin "3") (pinfunction "3_3") (pintype "unspecified"))
      (node (ref "SW71") (pin "3") (pinfunction "3_3") (pintype "unspecified"))
      (node (ref "SW8") (pin "3") (pinfunction "3_3") (pintype "unspecified"))
    )
    (net (code "9") (name "COL8") (class "Default")
      (node (ref "SW11") (pin "3") (pinfunction "3_3") (pintype "unspecified"))
      (node (ref "SW27") (pin "3") (pinfunction "3_3") (pintype "unspecified"))
      (node (ref "SW42") (pin "3") (pinfunction "3_3") (pintype "unspecified"))
      (node (ref "SW55") (pin "3") (pinfunction "3_3") (pintype "unspecified"))
      (node (ref "SW68") (pin "3") (pinfunction "3_3") (pintype "unspecified"))
    )
    (net (code "10") (name "COL9") (class "Default")
      (node (ref "SW10") (pin "3") (pinfunction "3_3") (pintype "unspecified"))
      (node (ref "SW24") (pin "3") (pinfunction "3_3") (pintype "unspecified"))
      (node (ref "SW45") (pin "3") (pinfunction "3_3") (pintype "unspecified"))
      (node (ref "SW56") (pin "3") (pinfunction "3_3") (pintype "unspecified"))
      (node (ref "SW69") (pin "3") (pinfunction "3_3") (pintype "unspecified"))
      (node (ref "SW83") (pin "3") (pinfunction "3_3") (pintype "unspecified"))
    )
    (net (code "11") (name "COL10") (class "Default")
      (node (ref "SW13") (pin "3") (pinfunction "3_3") (pintype "unspecified"))
      (node (ref "SW25") (pin "3") (pinfunction "3_3") (pintype "unspecified"))
      (node (ref "SW44") (pin "3") (pinfunction "3_3") (pintype "unspecified"))
      (node (ref "SW53") (pin "3") (pinfunction "3_3") (pintype "unspecified"))
      (node (ref "SW66") (pin "3") (pinfunction "3_3") (pintype "unspecified"))
      (node (ref "SW82") (pin "3") (pinfunction "3_3") (pintype "unspecified"))
    )
    (net (code "12") (name "COL11") (class "Default")
      (node (ref "SW12") (pin "3") (pinfunction "3_3") (pintype "unspecified"))
      (node (ref "SW22") (pin "3") (pinfunction "3_3") (pintype "unspecified"))
      (node (ref "SW47") (pin "3") (pinfunction "3_3") (pintype "unspecified"))
      (node (ref "SW54") (pin "3") (pinfunction "3_3") (pintype "unspecified"))
    )
    (net (code "13") (name "COL12") (class "Default")
      (node (ref "SW15") (pin "3") (pinfunction "3_3") (pintype "unspecified"))
      (node (ref "SW23") (pin "3") (pinfunction "3_3") (pintype "unspecified"))
      (node (ref "SW46") (pin "3") (pinfunction "3_3") (pintype "unspecified"))
      (node (ref "SW52") (pin "3") (pinfunction "3_3") (pintype "unspecified"))
      (node (ref "SW67") (pin "3") (pinfunction "3_3") (pintype "unspecified"))
      (node (ref "SW85") (pin "3") (pinfunction "3_3") (pintype "unspecified"))
    )
    (net (code "14") (name "COL13") (class "Default")
      (node (ref "SW14") (pin "3") (pinfunction "3_3") (pintype "unspecified"))
      (node (ref "SW20") (pin "3") (pinfunction "3_3") (pintype "unspecified"))
      (node (ref "SW49") (pin "3") (pinfunction "3_3") (pintype "unspecified"))
      (node (ref "SW84") (pin "3") (pinfunction "3_3") (pintype "unspecified"))
    )
    (net (code "15") (name "COL14") (class "Default")
      (node (ref "SW17") (pin "3") (pinfunction "3_3") (pintype "unspecified"))
      (node (ref "SW21") (pin "3") (pinfunction "3_3") (pintype "unspecified"))
      (node (ref "SW48") (pin "3") (pinfunction "3_3") (pintype "unspecified"))
      (node (ref "SW87") (pin "3") (pinfunction "3_3") (pintype "unspecified"))
    )
    (net (code "16") (name "COL15") (class "Default")
      (node (ref "SW16") (pin "3") (pinfunction "3_3") (pintype "unspecified"))
      (node (ref "SW18") (pin "3") (pinfunction "3_3") (pintype "unspecified"))
      (node (ref "SW51") (pin "3") (pinfunction "3_3") (pintype "unspecified"))
      (node (ref "SW65") (pin "3") (pinfunction "3_3") (pintype "unspecified"))
      (node (ref "SW86") (pin "3") (pinfunction "3_3") (pintype "unspecified"))
    )
    (net (code "17") (name "COL16") (class "Default")
      (node (ref "SW19") (pin "3") (pinfunction "3_3") (pintype "unspecified"))
      (node (ref "SW50") (pin "3") (pinfunction "3_3") (pintype "unspecified"))
      (node (ref "SW88") (pin "3") (pinfunction "3_3") (pintype "unspecified"))
    )
    (net (code "18") (name "D+") (class "Default")
      (node (ref "R4") (pin "2") (pinfunction "2_2") (pintype "unspecified"))
      (node (ref "U1") (pin "4") (pinfunction "D+_4") (pintype "unspecified"))
    )
    (net (code "19") (name "D-") (class "Default")
      (node (ref "R3") (pin "1") (pinfunction "1_1") (pintype "unspecified"))
      (node (ref "U1") (pin "3") (pinfunction "D-_3") (pintype "unspecified"))
    )
    (net (code "20") (name "GND") (class "Default")
      (node (ref "C1") (pin "2") (pinfunction "2_2") (pintype "unspecified"))
      (node (ref "C10") (pin "2") (pinfunction "2_2") (pintype "unspecified"))
      (node (ref "C11") (pin "2") (pinfunction "2_2") (pintype "unspecified"))
      (node (ref "C12") (pin "2") (pinfunction "2_2") (pintype "unspecified"))
      (node (ref "C13") (pin "2") (pinfunction "2_2") (pintype "unspecified"))
      (node (ref "C14") (pin "2") (pinfunction "2_2") (pintype "unspecified"))
      (node (ref "C15") (pin "2") (pinfunction "2_2") (pintype "unspecified"))
      (node (ref "C16") (pin "2") (pinfunction "2_2") (pintype "unspecified"))
      (node (ref "C17") (pin "2") (pinfunction "2_2") (pintype "unspecified"))
      (node (ref "C18") (pin "2") (pinfunction "2_2") (pintype "unspecified"))
      (node (ref "C19") (pin "2") (pinfunction "2_2") (pintype "unspecified"))
      (node (ref "C2") (pin "1") (pinfunction "1_1") (pintype "unspecified"))
      (node (ref "C20") (pin "2") (pinfunction "2_2") (pintype "unspecified"))
      (node (ref "C21") (pin "2") (pinfunction "2_2") (pintype "unspecified"))
      (node (ref "C22") (pin "2") (pinfunction "2_2") (pintype "unspecified"))
      (node (ref "C23") (pin "2") (pinfunction "2_2") (pintype "unspecified"))
      (node (ref "C24") (pin "2") (pinfunction "2_2") (pintype "unspecified"))
      (node (ref "C25") (pin "2") (pinfunction "2_2") (pintype "unspecified"))
      (node (ref "C26") (pin "2") (pinfunction "2_2") (pintype "unspecified"))
      (node (ref "C27") (pin "2") (pinfunction "2_2") (pintype "unspecified"))
      (node (ref "C28") (pin "2") (pinfunction "2_2") (pintype "unspecified"))
      (node (ref "C29") (pin "2") (pinfunction "2_2") (pintype "unspecified"))
      (node (ref "C3") (pin "1") (pinfunction "1_1") (pintype "unspecified"))
      (node (ref "C30") (pin "2") (pinfunction "2_2") (pintype "unspecified"))
      (node (ref "C31") (pin "2") (pinfunction "2_2") (pintype "unspecified"))
      (node (ref "C32") (pin "2") (pinfunction "2_2") (pintype "unspecified"))
      (node (ref "C33") (pin "2") (pinfunction "2_2") (pintype "unspecified"))
      (node (ref "C34") (pin "2") (pinfunction "2_2") (pintype "unspecified"))
      (node (ref "C35") (pin "2") (pinfunction "2_2") (pintype "unspecified"))
      (node (ref "C36") (pin "2") (pinfunction "2_2") (pintype "unspecified"))
      (node (ref "C37") (pin "2") (pinfunction "2_2") (pintype "unspecified"))
      (node (ref "C38") (pin "2") (pinfunction "2_2") (pintype "unspecified"))
      (node (ref "C39") (pin "2") (pinfunction "2_2") (pintype "unspecified"))
      (node (ref "C4") (pin "1") (pinfunction "1_1") (pintype "unspecified"))
      (node (ref "C40") (pin "2") (pinfunction "2_2") (pintype "unspecified"))
      (node (ref "C41") (pin "2") (pinfunction "2_2") (pintype "unspecified"))
      (node (ref "C42") (pin "2") (pinfunction "2_2") (pintype "unspecified"))
      (node (ref "C43") (pin "2") (pinfunction "2_2") (pintype "unspecified"))
      (node (ref "C44") (pin "2") (pinfunction "2_2") (pintype "unspecified"))
      (node (ref "C45") (pin "2") (pinfunction "2_2") (pintype "unspecified"))
      (node (ref "C46") (pin "2") (pinfunction "2_2") (pintype "unspecified"))
      (node (ref "C47") (pin "2") (pinfunction "2_2") (pintype "unspecified"))
      (node (ref "C48") (pin "2") (pinfunction "2_2") (pintype "unspecified"))
      (node (ref "C49") (pin "2") (pinfunction "2_2") (pintype "unspecified"))
      (node (ref "C5") (pin "1") (pinfunction "1_1") (pintype "unspecified"))
      (node (ref "C50") (pin "2") (pinfunction "2_2") (pintype "unspecified"))
      (node (ref "C51") (pin "2") (pinfunction "2_2") (pintype "unspecified"))
      (node (ref "C52") (pin "2") (pinfunction "2_2") (pintype "unspecified"))
      (node (ref "C53") (pin "2") (pinfunction "2_2") (pintype "unspecified"))
      (node (ref "C54") (pin "2") (pinfunction "2_2") (pintype "unspecified"))
      (node (ref "C55") (pin "2") (pinfunction "2_2") (pintype "unspecified"))
      (node (ref "C56") (pin "2") (pinfunction "2_2") (pintype "unspecified"))
      (node (ref "C57") (pin "2") (pinfunction "2_2") (pintype "unspecified"))
      (node (ref "C58") (pin "2") (pinfunction "2_2") (pintype "unspecified"))
      (node (ref "C59") (pin "2") (pinfunction "2_2") (pintype "unspecified"))
      (node (ref "C6") (pin "1") (pinfunction "1_1") (pintype "unspecified"))
      (node (ref "C60") (pin "2") (pinfunction "2_2") (pintype "unspecified"))
      (node (ref "C61") (pin "2") (pinfunction "2_2") (pintype "unspecified"))
      (node (ref "C62") (pin "2") (pinfunction "2_2") (pintype "unspecified"))
      (node (ref "C63") (pin "2") (pinfunction "2_2") (pintype "unspecified"))
      (node (ref "C64") (pin "2") (pinfunction "2_2") (pintype "unspecified"))
      (node (ref "C65") (pin "2") (pinfunction "2_2") (pintype "unspecified"))
      (node (ref "C66") (pin "2") (pinfunction "2_2") (pintype "unspecified"))
      (node (ref "C67") (pin "2") (pinfunction "2_2") (pintype "unspecified"))
      (node (ref "C68") (pin "2") (pinfunction "2_2") (pintype "unspecified"))
      (node (ref "C69") (pin "2") (pinfunction "2_2") (pintype "unspecified"))
      (node (ref "C7") (pin "1") (pinfunction "1_1") (pintype "unspecified"))
      (node (ref "C70") (pin "2") (pinfunction "2_2") (pintype "unspecified"))
      (node (ref "C71") (pin "2") (pinfunction "2_2") (pintype "unspecified"))
      (node (ref "C72") (pin "2") (pinfunction "2_2") (pintype "unspecified"))
      (node (ref "C73") (pin "2") (pinfunction "2_2") (pintype "unspecified"))
      (node (ref "C74") (pin "2") (pinfunction "2_2") (pintype "unspecified"))
      (node (ref "C75") (pin "2") (pinfunction "2_2") (pintype "unspecified"))
      (node (ref "C76") (pin "2") (pinfunction "2_2") (pintype "unspecified"))
      (node (ref "C77") (pin "2") (pinfunction "2_2") (pintype "unspecified"))
      (node (ref "C78") (pin "2") (pinfunction "2_2") (pintype "unspecified"))
      (node (ref "C79") (pin "2") (pinfunction "2_2") (pintype "unspecified"))
      (node (ref "C8") (pin "1") (pinfunction "1_1") (pintype "unspecified"))
      (node (ref "C80") (pin "2") (pinfunction "2_2") (pintype "unspecified"))
      (node (ref "C81") (pin "2") (pinfunction "2_2") (pintype "unspecified"))
      (node (ref "C82") (pin "2") (pinfunction "2_2") (pintype "unspecified"))
      (node (ref "C83") (pin "2") (pinfunction "2_2") (pintype "unspecified"))
      (node (ref "C84") (pin "2") (pinfunction "2_2") (pintype "unspecified"))
      (node (ref "C85") (pin "2") (pinfunction "2_2") (pintype "unspecified"))
      (node (ref "C86") (pin "2") (pinfunction "2_2") (pintype "unspecified"))
      (node (ref "C87") (pin "2") (pinfunction "2_2") (pintype "unspecified"))
      (node (ref "C88") (pin "2") (pinfunction "2_2") (pintype "unspecified"))
      (node (ref "C89") (pin "2") (pinfunction "2_2") (pintype "unspecified"))
      (node (ref "C9") (pin "2") (pinfunction "2_2") (pintype "unspecified"))
      (node (ref "C90") (pin "2") (pinfunction "2_2") (pintype "unspecified"))
      (node (ref "C91") (pin "2") (pinfunction "2_2") (pintype "unspecified"))
      (node (ref "C92") (pin "2") (pinfunction "2_2") (pintype "unspecified"))
      (node (ref "C93") (pin "2") (pinfunction "2_2") (pintype "unspecified"))
      (node (ref "C94") (pin "2") (pinfunction "2_2") (pintype "unspecified"))
      (node (ref "C96") (pin "2") (pinfunction "2_2") (pintype "unspecified"))
      (node (ref "R1") (pin "2") (pinfunction "2_2") (pintype "input"))
      (node (ref "SW1") (pin "1") (pinfunction "1_1") (pintype "unspecified"))
      (node (ref "SW10") (pin "5") (pinfunction "5_5") (pintype "unspecified"))
      (node (ref "SW11") (pin "5") (pinfunction "5_5") (pintype "unspecified"))
      (node (ref "SW12") (pin "5") (pinfunction "5_5") (pintype "unspecified"))
      (node (ref "SW13") (pin "5") (pinfunction "5_5") (pintype "unspecified"))
      (node (ref "SW14") (pin "5") (pinfunction "5_5") (pintype "unspecified"))
      (node (ref "SW15") (pin "5") (pinfunction "5_5") (pintype "unspecified"))
      (node (ref "SW16") (pin "5") (pinfunction "5_5") (pintype "unspecified"))
      (node (ref "SW17") (pin "5") (pinfunction "5_5") (pintype "unspecified"))
      (node (ref "SW18") (pin "5") (pinfunction "5_5") (pintype "unspecified"))
      (node (ref "SW19") (pin "5") (pinfunction "5_5") (pintype "unspecified"))
      (node (ref "SW2") (pin "5") (pinfunction "5_5") (pintype "unspecified"))
      (node (ref "SW20") (pin "5") (pinfunction "5_5") (pintype "unspecified"))
      (node (ref "SW21") (pin "5") (pinfunction "5_5") (pintype "unspecified"))
      (node (ref "SW22") (pin "5") (pinfunction "5_5") (pintype "unspecified"))
      (node (ref "SW23") (pin "5") (pinfunction "5_5") (pintype "unspecified"))
      (node (ref "SW24") (pin "5") (pinfunction "5_5") (pintype "unspecified"))
      (node (ref "SW25") (pin "5") (pinfunction "5_5") (pintype "unspecified"))
      (node (ref "SW26") (pin "5") (pinfunction "5_5") (pintype "unspecified"))
      (node (ref "SW27") (pin "5") (pinfunction "5_5") (pintype "unspecified"))
      (node (ref "SW28") (pin "5") (pinfunction "5_5") (pintype "unspecified"))
      (node (ref "SW29") (pin "5") (pinfunction "5_5") (pintype "unspecified"))
      (node (ref "SW3") (pin "5") (pinfunction "5_5") (pintype "unspecified"))
      (node (ref "SW30") (pin "5") (pinfunction "5_5") (pintype "unspecified"))
      (node (ref "SW31") (pin "5") (pinfunction "5_5") (pintype "unspecified"))
      (node (ref "SW32") (pin "5") (pinfunction "5_5") (pintype "unspecified"))
      (node (ref "SW33") (pin "5") (pinfunction "5_5") (pintype "unspecified"))
      (node (ref "SW34") (pin "5") (pinfunction "5_5") (pintype "unspecified"))
      (node (ref "SW35") (pin "5") (pinfunction "5_5") (pintype "unspecified"))
      (node (ref "SW36") (pin "5") (pinfunction "5_5") (pintype "unspecified"))
      (node (ref "SW37") (pin "5") (pinfunction "5_5") (pintype "unspecified"))
      (node (ref "SW38") (pin "5") (pinfunction "5_5") (pintype "unspecified"))
      (node (ref "SW39") (pin "5") (pinfunction "5_5") (pintype "unspecified"))
      (node (ref "SW4") (pin "5") (pinfunction "5_5") (pintype "unspecified"))
      (node (ref "SW40") (pin "5") (pinfunction "5_5") (pintype "unspecified"))
      (node (ref "SW41") (pin "5") (pinfunction "5_5") (pintype "unspecified"))
      (node (ref "SW42") (pin "5") (pinfunction "5_5") (pintype "unspecified"))
      (node (ref "SW43") (pin "5") (pinfunction "5_5") (pintype "unspecified"))
      (node (ref "SW44") (pin "5") (pinfunction "5_5") (pintype "unspecified"))
      (node (ref "SW45") (pin "5") (pinfunction "5_5") (pintype "unspecified"))
      (node (ref "SW46") (pin "5") (pinfunction "5_5") (pintype "unspecified"))
      (node (ref "SW47") (pin "5") (pinfunction "5_5") (pintype "unspecified"))
      (node (ref "SW48") (pin "5") (pinfunction "5_5") (pintype "unspecified"))
      (node (ref "SW49") (pin "5") (pinfunction "5_5") (pintype "unspecified"))
      (node (ref "SW5") (pin "5") (pinfunction "5_5") (pintype "unspecified"))
      (node (ref "SW50") (pin "5") (pinfunction "5_5") (pintype "unspecified"))
      (node (ref "SW51") (pin "5") (pinfunction "5_5") (pintype "unspecified"))
      (node (ref "SW52") (pin "5") (pinfunction "5_5") (pintype "unspecified"))
      (node (ref "SW53") (pin "5") (pinfunction "5_5") (pintype "unspecified"))
      (node (ref "SW54") (pin "5") (pinfunction "5_5") (pintype "unspecified"))
      (node (ref "SW55") (pin "5") (pinfunction "5_5") (pintype "unspecified"))
      (node (ref "SW56") (pin "5") (pinfunction "5_5") (pintype "unspecified"))
      (node (ref "SW57") (pin "5") (pinfunction "5_5") (pintype "unspecified"))
      (node (ref "SW58") (pin "5") (pinfunction "5_5") (pintype "unspecified"))
      (node (ref "SW59") (pin "5") (pinfunction "5_5") (pintype "unspecified"))
      (node (ref "SW6") (pin "5") (pinfunction "5_5") (pintype "unspecified"))
      (node (ref "SW60") (pin "5") (pinfunction "5_5") (pintype "unspecified"))
      (node (ref "SW61") (pin "5") (pinfunction "5_5") (pintype "unspecified"))
      (node (ref "SW62") (pin "5") (pinfunction "5_5") (pintype "unspecified"))
      (node (ref "SW63") (pin "5") (pinfunction "5_5") (pintype "unspecified"))
      (node (ref "SW64") (pin "5") (pinfunction "5_5") (pintype "unspecified"))
      (node (ref "SW65") (pin "5") (pinfunction "5_5") (pintype "unspecified"))
      (node (ref "SW66") (pin "5") (pinfunction "5_5") (pintype "unspecified"))
      (node (ref "SW67") (pin "5") (pinfunction "5_5") (pintype "unspecified"))
      (node (ref "SW68") (pin "5") (pinfunction "5_5") (pintype "unspecified"))
      (node (ref "SW69") (pin "5") (pinfunction "5_5") (pintype "unspecified"))
      (node (ref "SW7") (pin "5") (pinfunction "5_5") (pintype "unspecified"))
      (node (ref "SW70") (pin "5") (pinfunction "5_5") (pintype "unspecified"))
      (node (ref "SW71") (pin "5") (pinfunction "5_5") (pintype "unspecified"))
      (node (ref "SW72") (pin "5") (pinfunction "5_5") (pintype "unspecified"))
      (node (ref "SW73") (pin "5") (pinfunction "5_5") (pintype "unspecified"))
      (node (ref "SW74") (pin "5") (pinfunction "5_5") (pintype "unspecified"))
      (node (ref "SW75") (pin "5") (pinfunction "5_5") (pintype "unspecified"))
      (node (ref "SW76") (pin "5") (pinfunction "5_5") (pintype "unspecified"))
      (node (ref "SW77") (pin "5") (pinfunction "5_5") (pintype "unspecified"))
      (node (ref "SW78") (pin "5") (pinfunction "5_5") (pintype "unspecified"))
      (node (ref "SW79") (pin "5") (pinfunction "5_5") (pintype "unspecified"))
      (node (ref "SW8") (pin "5") (pinfunction "5_5") (pintype "unspecified"))
      (node (ref "SW80") (pin "5") (pinfunction "5_5") (pintype "unspecified"))
      (node (ref "SW81") (pin "5") (pinfunction "5_5") (pintype "unspecified"))
      (node (ref "SW82") (pin "5") (pinfunction "5_5") (pintype "unspecified"))
      (node (ref "SW83") (pin "5") (pinfunction "5_5") (pintype "unspecified"))
      (node (ref "SW84") (pin "5") (pinfunction "5_5") (pintype "unspecified"))
      (node (ref "SW85") (pin "5") (pinfunction "5_5") (pintype "unspecified"))
      (node (ref "SW86") (pin "5") (pinfunction "5_5") (pintype "unspecified"))
      (node (ref "SW87") (pin "5") (pinfunction "5_5") (pintype "unspecified"))
      (node (ref "SW88") (pin "5") (pinfunction "5_5") (pintype "unspecified"))
      (node (ref "SW9") (pin "5") (pinfunction "5_5") (pintype "unspecified"))
      (node (ref "U1") (pin "15") (pinfunction "GND_15") (pintype "unspecified"))
      (node (ref "U1") (pin "23") (pinfunction "GND_23") (pintype "unspecified"))
      (node (ref "U1") (pin "35") (pinfunction "GND_35") (pintype "unspecified"))
      (node (ref "U1") (pin "43") (pinfunction "GND_43") (pintype "unspecified"))
      (node (ref "U1") (pin "45") (pinfunction "EP_45") (pintype "unspecified"))
      (node (ref "U1") (pin "5") (pinfunction "UGnd_5") (pintype "unspecified"))
      (node (ref "U2") (pin "a4") (pinfunction "a_a4") (pintype "unspecified"))
      (node (ref "USBC1") (pin "0") (pinfunction "0_0") (pintype "unspecified"))
      (node (ref "USBC1") (pin "A1") (pinfunction "GND_A1") (pintype "unspecified"))
      (node (ref "USBC1") (pin "A12") (pinfunction "GND_A12") (pintype "unspecified"))
      (node (ref "USBC1") (pin "A4") (pinfunction "VBUS_A4") (pintype "unspecified"))
      (node (ref "USBC1") (pin "A9") (pinfunction "VBUS_A9") (pintype "unspecified"))
      (node (ref "USBC1") (pin "B1") (pinfunction "GND_B1") (pintype "unspecified"))
      (node (ref "USBC1") (pin "B12") (pinfunction "GND_B12") (pintype "unspecified"))
      (node (ref "USBC1") (pin "B4") (pinfunction "VBUS_B4") (pintype "unspecified"))
      (node (ref "USBC1") (pin "B9") (pinfunction "VBUS_B9") (pintype "unspecified"))
    )
    (net (code "21") (name "Net-(D1-A)") (class "Default")
      (node (ref "D1") (pin "2") (pinfunction "A_2") (pintype "unspecified"))
      (node (ref "SW2") (pin "4") (pinfunction "4_4") (pintype "unspecified"))
    )
    (net (code "22") (name "Net-(D2-A)") (class "Default")
      (node (ref "D2") (pin "2") (pinfunction "A_2") (pintype "unspecified"))
      (node (ref "SW3") (pin "4") (pinfunction "4_4") (pintype "unspecified"))
    )
    (net (code "23") (name "Net-(D3-A)") (class "Default")
      (node (ref "D3") (pin "2") (pinfunction "A_2") (pintype "unspecified"))
      (node (ref "SW4") (pin "4") (pinfunction "4_4") (pintype "unspecified"))
    )
    (net (code "24") (name "Net-(D4-A)") (class "Default")
      (node (ref "D4") (pin "2") (pinfunction "A_2") (pintype "unspecified"))
      (node (ref "SW5") (pin "4") (pinfunction "4_4") (pintype "unspecified"))
    )
    (net (code "25") (name "Net-(D5-A)") (class "Default")
      (node (ref "D5") (pin "2") (pinfunction "A_2") (pintype "unspecified"))
      (node (ref "SW6") (pin "4") (pinfunction "4_4") (pintype "unspecified"))
    )
    (net (code "26") (name "Net-(D6-A)") (class "Default")
      (node (ref "D6") (pin "2") (pinfunction "A_2") (pintype "unspecified"))
      (node (ref "SW7") (pin "4") (pinfunction "4_4") (pintype "unspecified"))
    )
    (net (code "27") (name "Net-(D7-A)") (class "Default")
      (node (ref "D7") (pin "2") (pinfunction "A_2") (pintype "unspecified"))
      (node (ref "SW8") (pin "4") (pinfunction "4_4") (pintype "unspecified"))
    )
    (net (code "28") (name "Net-(D8-A)") (class "Default")
      (node (ref "D8") (pin "2") (pinfunction "A_2") (pintype "unspecified"))
      (node (ref "SW9") (pin "4") (pinfunction "4_4") (pintype "unspecified"))
    )
    (net (code "29") (name "Net-(D9-A)") (class "Default")
      (node (ref "D9") (pin "2") (pinfunction "A_2") (pintype "unspecified"))
      (node (ref "SW10") (pin "4") (pinfunction "4_4") (pintype "unspecified"))
    )
    (net (code "30") (name "Net-(D10-A)") (class "Default")
      (node (ref "D10") (pin "2") (pinfunction "A_2") (pintype "unspecified"))
      (node (ref "SW11") (pin "4") (pinfunction "4_4") (pintype "unspecified"))
    )
    (net (code "31") (name "Net-(D11-A)") (class "Default")
      (node (ref "D11") (pin "2") (pinfunction "A_2") (pintype "unspecified"))
      (node (ref "SW12") (pin "4") (pinfunction "4_4") (pintype "unspecified"))
    )
    (net (code "32") (name "Net-(D12-A)") (class "Default")
      (node (ref "D12") (pin "2") (pinfunction "A_2") (pintype "unspecified"))
      (node (ref "SW13") (pin "4") (pinfunction "4_4") (pintype "unspecified"))
    )
    (net (code "33") (name "Net-(D13-A)") (class "Default")
      (node (ref "D13") (pin "2") (pinfunction "A_2") (pintype "unspecified"))
      (node (ref "SW14") (pin "4") (pinfunction "4_4") (pintype "unspecified"))
    )
    (net (code "34") (name "Net-(D14-A)") (class "Default")
      (node (ref "D14") (pin "2") (pinfunction "A_2") (pintype "unspecified"))
      (node (ref "SW15") (pin "4") (pinfunction "4_4") (pintype "unspecified"))
    )
    (net (code "35") (name "Net-(D15-A)") (class "Default")
      (node (ref "D15") (pin "2") (pinfunction "A_2") (pintype "unspecified"))
      (node (ref "SW16") (pin "4") (pinfunction "4_4") (pintype "unspecified"))
    )
    (net (code "36") (name "Net-(D16-A)") (class "Default")
      (node (ref "D16") (pin "2") (pinfunction "A_2") (pintype "unspecified"))
      (node (ref "SW17") (pin "4") (pinfunction "4_4") (pintype "unspecified"))
    )
    (net (code "37") (name "Net-(D17-A)") (class "Default")
      (node (ref "D17") (pin "2") (pinfunction "A_2") (pintype "unspecified"))
      (node (ref "SW18") (pin "4") (pinfunction "4_4") (pintype "unspecified"))
    )
    (net (code "38") (name "Net-(D18-A)") (class "Default")
      (node (ref "D18") (pin "2") (pinfunction "A_2") (pintype "unspecified"))
      (node (ref "SW19") (pin "4") (pinfunction "4_4") (pintype "unspecified"))
    )
    (net (code "39") (name "Net-(D19-A)") (class "Default")
      (node (ref "D19") (pin "2") (pinfunction "A_2") (pintype "unspecified"))
      (node (ref "SW20") (pin "4") (pinfunction "4_4") (pintype "unspecified"))
    )
    (net (code "40") (name "Net-(D20-A)") (class "Default")
      (node (ref "D20") (pin "2") (pinfunction "A_2") (pintype "unspecified"))
      (node (ref "SW21") (pin "4") (pinfunction "4_4") (pintype "unspecified"))
    )
    (net (code "41") (name "Net-(D21-A)") (class "Default")
      (node (ref "D21") (pin "2") (pinfunction "A_2") (pintype "unspecified"))
      (node (ref "SW22") (pin "4") (pinfunction "4_4") (pintype "unspecified"))
    )
    (net (code "42") (name "Net-(D22-A)") (class "Default")
      (node (ref "D22") (pin "2") (pinfunction "A_2") (pintype "unspecified"))
      (node (ref "SW23") (pin "4") (pinfunction "4_4") (pintype "unspecified"))
    )
    (net (code "43") (name "Net-(D23-A)") (class "Default")
      (node (ref "D23") (pin "2") (pinfunction "A_2") (pintype "unspecified"))
      (node (ref "SW24") (pin "4") (pinfunction "4_4") (pintype "unspecified"))
    )
    (net (code "44") (name "Net-(D24-A)") (class "Default")
      (node (ref "D24") (pin "2") (pinfunction "A_2") (pintype "unspecified"))
      (node (ref "SW25") (pin "4") (pinfunction "4_4") (pintype "unspecified"))
    )
    (net (code "45") (name "Net-(D25-A)") (class "Default")
      (node (ref "D25") (pin "2") (pinfunction "A_2") (pintype "unspecified"))
      (node (ref "SW26") (pin "4") (pinfunction "4_4") (pintype "unspecified"))
    )
    (net (code "46") (name "Net-(D26-A)") (class "Default")
      (node (ref "D26") (pin "2") (pinfunction "A_2") (pintype "unspecified"))
      (node (ref "SW27") (pin "4") (pinfunction "4_4") (pintype "unspecified"))
    )
    (net (code "47") (name "Net-(D27-A)") (class "Default")
      (node (ref "D27") (pin "2") (pinfunction "A_2") (pintype "unspecified"))
      (node (ref "SW28") (pin "4") (pinfunction "4_4") (pintype "unspecified"))
    )
    (net (code "48") (name "Net-(D28-A)") (class "Default")
      (node (ref "D28") (pin "2") (pinfunction "A_2") (pintype "unspecified"))
      (node (ref "SW29") (pin "4") (pinfunction "4_4") (pintype "unspecified"))
    )
    (net (code "49") (name "Net-(D29-A)") (class "Default")
      (node (ref "D29") (pin "2") (pinfunction "A_2") (pintype "unspecified"))
      (node (ref "SW30") (pin "4") (pinfunction "4_4") (pintype "unspecified"))
    )
    (net (code "50") (name "Net-(D30-A)") (class "Default")
      (node (ref "D30") (pin "2") (pinfunction "A_2") (pintype "unspecified"))
      (node (ref "SW31") (pin "4") (pinfunction "4_4") (pintype "unspecified"))
    )
    (net (code "51") (name "Net-(D31-A)") (class "Default")
      (node (ref "D31") (pin "2") (pinfunction "A_2") (pintype "unspecified"))
      (node (ref "SW32") (pin "4") (pinfunction "4_4") (pintype "unspecified"))
    )
    (net (code "52") (name "Net-(D32-A)") (class "Default")
      (node (ref "D32") (pin "2") (pinfunction "A_2") (pintype "unspecified"))
      (node (ref "SW33") (pin "4") (pinfunction "4_4") (pintype "unspecified"))
    )
    (net (code "53") (name "Net-(D33-A)") (class "Default")
      (node (ref "D33") (pin "2") (pinfunction "A_2") (pintype "unspecified"))
      (node (ref "SW34") (pin "4") (pinfunction "4_4") (pintype "unspecified"))
    )
    (net (code "54") (name "Net-(D34-A)") (class "Default")
      (node (ref "D34") (pin "2") (pinfunction "A_2") (pintype "unspecified"))
      (node (ref "SW35") (pin "4") (pinfunction "4_4") (pintype "unspecified"))
    )
    (net (code "55") (name "Net-(D35-A)") (class "Default")
      (node (ref "D35") (pin "2") (pinfunction "A_2") (pintype "unspecified"))
      (node (ref "SW36") (pin "4") (pinfunction "4_4") (pintype "unspecified"))
    )
    (net (code "56") (name "Net-(D36-A)") (class "Default")
      (node (ref "D36") (pin "2") (pinfunction "A_2") (pintype "unspecified"))
      (node (ref "SW37") (pin "4") (pinfunction "4_4") (pintype "unspecified"))
    )
    (net (code "57") (name "Net-(D37-A)") (class "Default")
      (node (ref "D37") (pin "2") (pinfunction "A_2") (pintype "unspecified"))
      (node (ref "SW38") (pin "4") (pinfunction "4_4") (pintype "unspecified"))
    )
    (net (code "58") (name "Net-(D38-A)") (class "Default")
      (node (ref "D38") (pin "2") (pinfunction "A_2") (pintype "unspecified"))
      (node (ref "SW39") (pin "4") (pinfunction "4_4") (pintype "unspecified"))
    )
    (net (code "59") (name "Net-(D39-A)") (class "Default")
      (node (ref "D39") (pin "2") (pinfunction "A_2") (pintype "unspecified"))
      (node (ref "SW40") (pin "4") (pinfunction "4_4") (pintype "unspecified"))
    )
    (net (code "60") (name "Net-(D40-A)") (class "Default")
      (node (ref "D40") (pin "2") (pinfunction "A_2") (pintype "unspecified"))
      (node (ref "SW41") (pin "4") (pinfunction "4_4") (pintype "unspecified"))
    )
    (net (code "61") (name "Net-(D41-A)") (class "Default")
      (node (ref "D41") (pin "2") (pinfunction "A_2") (pintype "unspecified"))
      (node (ref "SW42") (pin "4") (pinfunction "4_4") (pintype "unspecified"))
    )
    (net (code "62") (name "Net-(D42-A)") (class "Default")
      (node (ref "D42") (pin "2") (pinfunction "A_2") (pintype "unspecified"))
      (node (ref "SW43") (pin "4") (pinfunction "4_4") (pintype "unspecified"))
    )
    (net (code "63") (name "Net-(D43-A)") (class "Default")
      (node (ref "D43") (pin "2") (pinfunction "A_2") (pintype "unspecified"))
      (node (ref "SW44") (pin "4") (pinfunction "4_4") (pintype "unspecified"))
    )
    (net (code "64") (name "Net-(D44-A)") (class "Default")
      (node (ref "D44") (pin "2") (pinfunction "A_2") (pintype "unspecified"))
      (node (ref "SW45") (pin "4") (pinfunction "4_4") (pintype "unspecified"))
    )
    (net (code "65") (name "Net-(D45-A)") (class "Default")
      (node (ref "D45") (pin "2") (pinfunction "A_2") (pintype "unspecified"))
      (node (ref "SW46") (pin "4") (pinfunction "4_4") (pintype "unspecified"))
    )
    (net (code "66") (name "Net-(D46-A)") (class "Default")
      (node (ref "D46") (pin "2") (pinfunction "A_2") (pintype "unspecified"))
      (node (ref "SW47") (pin "4") (pinfunction "4_4") (pintype "unspecified"))
    )
    (net (code "67") (name "Net-(D47-A)") (class "Default")
      (node (ref "D47") (pin "2") (pinfunction "A_2") (pintype "unspecified"))
      (node (ref "SW48") (pin "4") (pinfunction "4_4") (pintype "unspecified"))
    )
    (net (code "68") (name "Net-(D48-A)") (class "Default")
      (node (ref "D48") (pin "2") (pinfunction "A_2") (pintype "unspecified"))
      (node (ref "SW49") (pin "4") (pinfunction "4_4") (pintype "unspecified"))
    )
    (net (code "69") (name "Net-(D49-A)") (class "Default")
      (node (ref "D49") (pin "2") (pinfunction "A_2") (pintype "unspecified"))
      (node (ref "SW51") (pin "4") (pinfunction "4_4") (pintype "unspecified"))
    )
    (net (code "70") (name "Net-(D50-A)") (class "Default")
      (node (ref "D50") (pin "2") (pinfunction "A_2") (pintype "unspecified"))
      (node (ref "SW50") (pin "4") (pinfunction "4_4") (pintype "unspecified"))
    )
    (net (code "71") (name "Net-(D51-A)") (class "Default")
      (node (ref "D51") (pin "2") (pinfunction "A_2") (pintype "unspecified"))
      (node (ref "SW53") (pin "4") (pinfunction "4_4") (pintype "unspecified"))
    )
    (net (code "72") (name "Net-(D52-A)") (class "Default")
      (node (ref "D52") (pin "2") (pinfunction "A_2") (pintype "unspecified"))
      (node (ref "SW54") (pin "4") (pinfunction "4_4") (pintype "unspecified"))
    )
    (net (code "73") (name "Net-(D53-A)") (class "Default")
      (node (ref "D53") (pin "2") (pinfunction "A_2") (pintype "unspecified"))
      (node (ref "SW55") (pin "4") (pinfunction "4_4") (pintype "unspecified"))
    )
    (net (code "74") (name "Net-(D54-A)") (class "Default")
      (node (ref "D54") (pin "2") (pinfunction "A_2") (pintype "unspecified"))
      (node (ref "SW56") (pin "4") (pinfunction "4_4") (pintype "unspecified"))
    )
    (net (code "75") (name "Net-(D55-A)") (class "Default")
      (node (ref "D55") (pin "2") (pinfunction "A_2") (pintype "unspecified"))
      (node (ref "SW57") (pin "4") (pinfunction "4_4") (pintype "unspecified"))
    )
    (net (code "76") (name "Net-(D56-A)") (class "Default")
      (node (ref "D56") (pin "2") (pinfunction "A_2") (pintype "unspecified"))
      (node (ref "SW58") (pin "4") (pinfunction "4_4") (pintype "unspecified"))
    )
    (net (code "77") (name "Net-(D57-A)") (class "Default")
      (node (ref "D57") (pin "2") (pinfunction "A_2") (pintype "unspecified"))
      (node (ref "SW59") (pin "4") (pinfunction "4_4") (pintype "unspecified"))
    )
    (net (code "78") (name "Net-(D58-A)") (class "Default")
      (node (ref "D58") (pin "2") (pinfunction "A_2") (pintype "unspecified"))
      (node (ref "SW60") (pin "4") (pinfunction "4_4") (pintype "unspecified"))
    )
    (net (code "79") (name "Net-(D59-A)") (class "Default")
      (node (ref "D59") (pin "2") (pinfunction "A_2") (pintype "unspecified"))
      (node (ref "SW61") (pin "4") (pinfunction "4_4") (pintype "unspecified"))
    )
    (net (code "80") (name "Net-(D60-A)") (class "Default")
      (node (ref "D60") (pin "2") (pinfunction "A_2") (pintype "unspecified"))
      (node (ref "SW62") (pin "4") (pinfunction "4_4") (pintype "unspecified"))
    )
    (net (code "81") (name "Net-(D61-A)") (class "Default")
      (node (ref "D61") (pin "2") (pinfunction "A_2") (pintype "unspecified"))
      (node (ref "SW63") (pin "4") (pinfunction "4_4") (pintype "unspecified"))
    )
    (net (code "82") (name "Net-(D62-A)") (class "Default")
      (node (ref "D62") (pin "2") (pinfunction "A_2") (pintype "unspecified"))
      (node (ref "SW64") (pin "4") (pinfunction "4_4") (pintype "unspecified"))
    )
    (net (code "83") (name "Net-(D63-A)") (class "Default")
      (node (ref "D63") (pin "2") (pinfunction "A_2") (pintype "unspecified"))
      (node (ref "SW52") (pin "4") (pinfunction "4_4") (pintype "unspecified"))
    )
    (net (code "84") (name "Net-(D64-A)") (class "Default")
      (node (ref "D64") (pin "2") (pinfunction "A_2") (pintype "unspecified"))
      (node (ref "SW66") (pin "4") (pinfunction "4_4") (pintype "unspecified"))
    )
    (net (code "85") (name "Net-(D65-A)") (class "Default")
      (node (ref "D65") (pin "2") (pinfunction "A_2") (pintype "unspecified"))
      (node (ref "SW67") (pin "4") (pinfunction "4_4") (pintype "unspecified"))
    )
    (net (code "86") (name "Net-(D66-A)") (class "Default")
      (node (ref "D66") (pin "2") (pinfunction "A_2") (pintype "unspecified"))
      (node (ref "SW68") (pin "4") (pinfunction "4_4") (pintype "unspecified"))
    )
    (net (code "87") (name "Net-(D67-A)") (class "Default")
      (node (ref "D67") (pin "2") (pinfunction "A_2") (pintype "unspecified"))
      (node (ref "SW69") (pin "4") (pinfunction "4_4") (pintype "unspecified"))
    )
    (net (code "88") (name "Net-(D68-A)") (class "Default")
      (node (ref "D68") (pin "2") (pinfunction "A_2") (pintype "unspecified"))
      (node (ref "SW70") (pin "4") (pinfunction "4_4") (pintype "unspecified"))
    )
    (net (code "89") (name "Net-(D69-A)") (class "Default")
      (node (ref "D69") (pin "2") (pinfunction "A_2") (pintype "unspecified"))
      (node (ref "SW71") (pin "4") (pinfunction "4_4") (pintype "unspecified"))
    )
    (net (code "90") (name "Net-(D70-A)") (class "Default")
      (node (ref "D70") (pin "2") (pinfunction "A_2") (pintype "unspecified"))
      (node (ref "SW72") (pin "4") (pinfunction "4_4") (pintype "unspecified"))
    )
    (net (code "91") (name "Net-(D71-A)") (class "Default")
      (node (ref "D71") (pin "2") (pinfunction "A_2") (pintype "unspecified"))
      (node (ref "SW73") (pin "4") (pinfunction "4_4") (pintype "unspecified"))
    )
    (net (code "92") (name "Net-(D72-A)") (class "Default")
      (node (ref "D72") (pin "2") (pinfunction "A_2") (pintype "unspecified"))
      (node (ref "SW74") (pin "4") (pinfunction "4_4") (pintype "unspecified"))
    )
    (net (code "93") (name "Net-(D73-A)") (class "Default")
      (node (ref "D73") (pin "2") (pinfunction "A_2") (pintype "unspecified"))
      (node (ref "SW75") (pin "4") (pinfunction "4_4") (pintype "unspecified"))
    )
    (net (code "94") (name "Net-(D74-A)") (class "Default")
      (node (ref "D74") (pin "2") (pinfunction "A_2") (pintype "unspecified"))
      (node (ref "SW76") (pin "4") (pinfunction "4_4") (pintype "unspecified"))
    )
    (net (code "95") (name "Net-(D75-A)") (class "Default")
      (node (ref "D75") (pin "2") (pinfunction "A_2") (pintype "unspecified"))
      (node (ref "SW77") (pin "4") (pinfunction "4_4") (pintype "unspecified"))
    )
    (net (code "96") (name "Net-(D76-A)") (class "Default")
      (node (ref "D76") (pin "2") (pinfunction "A_2") (pintype "unspecified"))
      (node (ref "SW65") (pin "4") (pinfunction "4_4") (pintype "unspecified"))
    )
    (net (code "97") (name "Net-(D77-A)") (class "Default")
      (node (ref "D77") (pin "2") (pinfunction "A_2") (pintype "unspecified"))
      (node (ref "SW78") (pin "4") (pinfunction "4_4") (pintype "unspecified"))
    )
    (net (code "98") (name "Net-(D78-A)") (class "Default")
      (node (ref "D78") (pin "2") (pinfunction "A_2") (pintype "unspecified"))
      (node (ref "SW79") (pin "4") (pinfunction "4_4") (pintype "unspecified"))
    )
    (net (code "99") (name "Net-(D79-A)") (class "Default")
      (node (ref "D79") (pin "2") (pinfunction "A_2") (pintype "unspecified"))
      (node (ref "SW80") (pin "4") (pinfunction "4_4") (pintype "unspecified"))
    )
    (net (code "100") (name "Net-(D80-A)") (class "Default")
      (node (ref "D80") (pin "2") (pinfunction "A_2") (pintype "unspecified"))
      (node (ref "SW81") (pin "4") (pinfunction "4_4") (pintype "unspecified"))
    )
    (net (code "101") (name "Net-(D81-A)") (class "Default")
      (node (ref "D81") (pin "2") (pinfunction "A_2") (pintype "unspecified"))
      (node (ref "SW82") (pin "4") (pinfunction "4_4") (pintype "unspecified"))
    )
    (net (code "102") (name "Net-(D82-A)") (class "Default")
      (node (ref "D82") (pin "2") (pinfunction "A_2") (pintype "unspecified"))
      (node (ref "SW83") (pin "4") (pinfunction "4_4") (pintype "unspecified"))
    )
    (net (code "103") (name "Net-(D83-A)") (class "Default")
      (node (ref "D83") (pin "2") (pinfunction "A_2") (pintype "unspecified"))
      (node (ref "SW84") (pin "4") (pinfunction "4_4") (pintype "unspecified"))
    )
    (net (code "104") (name "Net-(D84-A)") (class "Default")
      (node (ref "D84") (pin "2") (pinfunction "A_2") (pintype "unspecified"))
      (node (ref "SW85") (pin "4") (pinfunction "4_4") (pintype "unspecified"))
    )
    (net (code "105") (name "Net-(D85-A)") (class "Default")
      (node (ref "D85") (pin "2") (pinfunction "A_2") (pintype "unspecified"))
      (node (ref "SW86") (pin "4") (pinfunction "4_4") (pintype "unspecified"))
    )
    (net (code "106") (name "Net-(D86-A)") (class "Default")
      (node (ref "D86") (pin "2") (pinfunction "A_2") (pintype "unspecified"))
      (node (ref "SW87") (pin "4") (pinfunction "4_4") (pintype "unspecified"))
    )
    (net (code "107") (name "Net-(D87-A)") (class "Default")
      (node (ref "D87") (pin "2") (pinfunction "A_2") (pintype "unspecified"))
      (node (ref "SW88") (pin "4") (pinfunction "4_4") (pintype "unspecified"))
    )
    (net (code "108") (name "Net-(SW2-Pad2)") (class "Default")
      (node (ref "SW2") (pin "2") (pinfunction "2_2") (pintype "unspecified"))
      (node (ref "SW3") (pin "6") (pinfunction "6_6") (pintype "unspecified"))
    )
    (net (code "109") (name "Net-(SW3-Pad2)") (class "Default")
      (node (ref "SW3") (pin "2") (pinfunction "2_2") (pintype "unspecified"))
      (node (ref "SW5") (pin "6") (pinfunction "6_6") (pintype "unspecified"))
    )
    (net (code "110") (name "Net-(SW4-Pad2)") (class "Default")
      (node (ref "SW4") (pin "2") (pinfunction "2_2") (pintype "unspecified"))
      (node (ref "SW7") (pin "6") (pinfunction "6_6") (pintype "unspecified"))
    )
    (net (code "111") (name "Net-(SW4-Pad6)") (class "Default")
      (node (ref "SW4") (pin "6") (pinfunction "6_6") (pintype "unspecified"))
      (node (ref "SW5") (pin "2") (pinfunction "2_2") (pintype "unspecified"))
    )
    (net (code "112") (name "Net-(SW6-Pad2)") (class "Default")
      (node (ref "SW6") (pin "2") (pinfunction "2_2") (pintype "unspecified"))
      (node (ref "SW9") (pin "6") (pinfunction "6_6") (pintype "unspecified"))
    )
    (net (code "113") (name "Net-(SW6-Pad6)") (class "Default")
      (node (ref "SW6") (pin "6") (pinfunction "6_6") (pintype "unspecified"))
      (node (ref "SW7") (pin "2") (pinfunction "2_2") (pintype "unspecified"))
    )
    (net (code "114") (name "Net-(SW8-Pad6)") (class "Default")
      (node (ref "SW8") (pin "6") (pinfunction "6_6") (pintype "unspecified"))
      (node (ref "SW9") (pin "2") (pinfunction "2_2") (pintype "unspecified"))
    )
    (net (code "115") (name "Net-(SW10-Pad2)") (class "Default")
      (node (ref "SW10") (pin "2") (pinfunction "2_2") (pintype "unspecified"))
      (node (ref "SW13") (pin "6") (pinfunction "6_6") (pintype "unspecified"))
    )
    (net (code "116") (name "Net-(SW10-Pad6)") (class "Default")
      (node (ref "SW10") (pin "6") (pinfunction "6_6") (pintype "unspecified"))
      (node (ref "SW11") (pin "2") (pinfunction "2_2") (pintype "unspecified"))
    )
    (net (code "117") (name "Net-(SW11-Pad6)") (class "Default")
      (node (ref "SW11") (pin "6") (pinfunction "6_6") (pintype "unspecified"))
      (node (ref "SW8") (pin "2") (pinfunction "2_2") (pintype "unspecified"))
    )
    (net (code "118") (name "Net-(SW12-Pad2)") (class "Default")
      (node (ref "SW12") (pin "2") (pinfunction "2_2") (pintype "unspecified"))
      (node (ref "SW15") (pin "6") (pinfunction "6_6") (pintype "unspecified"))
    )
    (net (code "119") (name "Net-(SW12-Pad6)") (class "Default")
      (node (ref "SW12") (pin "6") (pinfunction "6_6") (pintype "unspecified"))
      (node (ref "SW13") (pin "2") (pinfunction "2_2") (pintype "unspecified"))
    )
    (net (code "120") (name "Net-(SW14-Pad2)") (class "Default")
      (node (ref "SW14") (pin "2") (pinfunction "2_2") (pintype "unspecified"))
      (node (ref "SW17") (pin "6") (pinfunction "6_6") (pintype "unspecified"))
    )
    (net (code "121") (name "Net-(SW14-Pad6)") (class "Default")
      (node (ref "SW14") (pin "6") (pinfunction "6_6") (pintype "unspecified"))
      (node (ref "SW15") (pin "2") (pinfunction "2_2") (pintype "unspecified"))
    )
    (net (code "122") (name "Net-(SW16-Pad6)") (class "Default")
      (node (ref "SW16") (pin "6") (pinfunction "6_6") (pintype "unspecified"))
      (node (ref "SW17") (pin "2") (pinfunction "2_2") (pintype "unspecified"))
    )
    (net (code "123") (name "Net-(SW18-Pad2)") (class "Default")
      (node (ref "SW18") (pin "2") (pinfunction "2_2") (pintype "unspecified"))
      (node (ref "SW19") (pin "6") (pinfunction "6_6") (pintype "unspecified"))
    )
    (net (code "124") (name "Net-(SW18-Pad6)") (class "Default")
      (node (ref "SW18") (pin "6") (pinfunction "6_6") (pintype "unspecified"))
      (node (ref "SW21") (pin "2") (pinfunction "2_2") (pintype "unspecified"))
    )
    (net (code "125") (name "Net-(SW20-Pad2)") (class "Default")
      (node (ref "SW20") (pin "2") (pinfunction "2_2") (pintype "unspecified"))
      (node (ref "SW21") (pin "6") (pinfunction "6_6") (pintype "unspecified"))
    )
    (net (code "126") (name "Net-(SW20-Pad6)") (class "Default")
      (node (ref "SW20") (pin "6") (pinfunction "6_6") (pintype "unspecified"))
      (node (ref "SW23") (pin "2") (pinfunction "2_2") (pintype "unspecified"))
    )
    (net (code "127") (name "Net-(SW22-Pad2)") (class "Default")
      (node (ref "SW22") (pin "2") (pinfunction "2_2") (pintype "unspecified"))
      (node (ref "SW23") (pin "6") (pinfunction "6_6") (pintype "unspecified"))
    )
    (net (code "128") (name "Net-(SW22-Pad6)") (class "Default")
      (node (ref "SW22") (pin "6") (pinfunction "6_6") (pintype "unspecified"))
      (node (ref "SW25") (pin "2") (pinfunction "2_2") (pintype "unspecified"))
    )
    (net (code "129") (name "Net-(SW24-Pad2)") (class "Default")
      (node (ref "SW24") (pin "2") (pinfunction "2_2") (pintype "unspecified"))
      (node (ref "SW25") (pin "6") (pinfunction "6_6") (pintype "unspecified"))
    )
    (net (code "130") (name "Net-(SW24-Pad6)") (class "Default")
      (node (ref "SW24") (pin "6") (pinfunction "6_6") (pintype "unspecified"))
      (node (ref "SW27") (pin "2") (pinfunction "2_2") (pintype "unspecified"))
    )
    (net (code "131") (name "Net-(SW26-Pad2)") (class "Default")
      (node (ref "SW26") (pin "2") (pinfunction "2_2") (pintype "unspecified"))
      (node (ref "SW27") (pin "6") (pinfunction "6_6") (pintype "unspecified"))
    )
    (net (code "132") (name "Net-(SW26-Pad6)") (class "Default")
      (node (ref "SW26") (pin "6") (pinfunction "6_6") (pintype "unspecified"))
      (node (ref "SW29") (pin "2") (pinfunction "2_2") (pintype "unspecified"))
    )
    (net (code "133") (name "Net-(SW28-Pad2)") (class "Default")
      (node (ref "SW28") (pin "2") (pinfunction "2_2") (pintype "unspecified"))
      (node (ref "SW29") (pin "6") (pinfunction "6_6") (pintype "unspecified"))
    )
    (net (code "134") (name "Net-(SW28-Pad6)") (class "Default")
      (node (ref "SW28") (pin "6") (pinfunction "6_6") (pintype "unspecified"))
      (node (ref "SW31") (pin "2") (pinfunction "2_2") (pintype "unspecified"))
    )
    (net (code "135") (name "Net-(SW30-Pad2)") (class "Default")
      (node (ref "SW30") (pin "2") (pinfunction "2_2") (pintype "unspecified"))
      (node (ref "SW31") (pin "6") (pinfunction "6_6") (pintype "unspecified"))
    )
    (net (code "136") (name "Net-(SW30-Pad6)") (class "Default")
      (node (ref "SW30") (pin "6") (pinfunction "6_6") (pintype "unspecified"))
      (node (ref "SW32") (pin "2") (pinfunction "2_2") (pintype "unspecified"))
    )
    (net (code "137") (name "Net-(SW32-Pad6)") (class "Default")
      (node (ref "SW32") (pin "6") (pinfunction "6_6") (pintype "unspecified"))
      (node (ref "SW33") (pin "2") (pinfunction "2_2") (pintype "unspecified"))
    )
    (net (code "138") (name "Net-(SW33-Pad6)") (class "Default")
      (node (ref "SW33") (pin "6") (pinfunction "6_6") (pintype "unspecified"))
      (node (ref "SW34") (pin "2") (pinfunction "2_2") (pintype "unspecified"))
    )
    (net (code "139") (name "Net-(SW35-Pad2)") (class "Default")
      (node (ref "SW35") (pin "2") (pinfunction "2_2") (pintype "unspecified"))
      (node (ref "SW36") (pin "6") (pinfunction "6_6") (pintype "unspecified"))
    )
    (net (code "140") (name "Net-(SW36-Pad2)") (class "Default")
      (node (ref "SW36") (pin "2") (pinfunction "2_2") (pintype "unspecified"))
      (node (ref "SW37") (pin "6") (pinfunction "6_6") (pintype "unspecified"))
    )
    (net (code "141") (name "Net-(SW37-Pad2)") (class "Default")
      (node (ref "SW37") (pin "2") (pinfunction "2_2") (pintype "unspecified"))
      (node (ref "SW39") (pin "6") (pinfunction "6_6") (pintype "unspecified"))
    )
    (net (code "142") (name "Net-(SW38-Pad2)") (class "Default")
      (node (ref "SW38") (pin "2") (pinfunction "2_2") (pintype "unspecified"))
      (node (ref "SW41") (pin "6") (pinfunction "6_6") (pintype "unspecified"))
    )
    (net (code "143") (name "Net-(SW38-Pad6)") (class "Default")
      (node (ref "SW38") (pin "6") (pinfunction "6_6") (pintype "unspecified"))
      (node (ref "SW39") (pin "2") (pinfunction "2_2") (pintype "unspecified"))
    )
    (net (code "144") (name "Net-(SW40-Pad2)") (class "Default")
      (node (ref "SW40") (pin "2") (pinfunction "2_2") (pintype "unspecified"))
      (node (ref "SW43") (pin "6") (pinfunction "6_6") (pintype "unspecified"))
    )
    (net (code "145") (name "Net-(SW40-Pad6)") (class "Default")
      (node (ref "SW40") (pin "6") (pinfunction "6_6") (pintype "unspecified"))
      (node (ref "SW41") (pin "2") (pinfunction "2_2") (pintype "unspecified"))
    )
    (net (code "146") (name "Net-(SW42-Pad2)") (class "Default")
      (node (ref "SW42") (pin "2") (pinfunction "2_2") (pintype "unspecified"))
      (node (ref "SW45") (pin "6") (pinfunction "6_6") (pintype "unspecified"))
    )
    (net (code "147") (name "Net-(SW42-Pad6)") (class "Default")
      (node (ref "SW42") (pin "6") (pinfunction "6_6") (pintype "unspecified"))
      (node (ref "SW43") (pin "2") (pinfunction "2_2") (pintype "unspecified"))
    )
    (net (code "148") (name "Net-(SW44-Pad2)") (class "Default")
      (node (ref "SW44") (pin "2") (pinfunction "2_2") (pintype "unspecified"))
      (node (ref "SW47") (pin "6") (pinfunction "6_6") (pintype "unspecified"))
    )
    (net (code "149") (name "Net-(SW44-Pad6)") (class "Default")
      (node (ref "SW44") (pin "6") (pinfunction "6_6") (pintype "unspecified"))
      (node (ref "SW45") (pin "2") (pinfunction "2_2") (pintype "unspecified"))
    )
    (net (code "150") (name "Net-(SW46-Pad2)") (class "Default")
      (node (ref "SW46") (pin "2") (pinfunction "2_2") (pintype "unspecified"))
      (node (ref "SW49") (pin "6") (pinfunction "6_6") (pintype "unspecified"))
    )
    (net (code "151") (name "Net-(SW46-Pad6)") (class "Default")
      (node (ref "SW46") (pin "6") (pinfunction "6_6") (pintype "unspecified"))
      (node (ref "SW47") (pin "2") (pinfunction "2_2") (pintype "unspecified"))
    )
    (net (code "152") (name "Net-(SW48-Pad2)") (class "Default")
      (node (ref "SW48") (pin "2") (pinfunction "2_2") (pintype "unspecified"))
      (node (ref "SW51") (pin "6") (pinfunction "6_6") (pintype "unspecified"))
    )
    (net (code "153") (name "Net-(SW48-Pad6)") (class "Default")
      (node (ref "SW48") (pin "6") (pinfunction "6_6") (pintype "unspecified"))
      (node (ref "SW49") (pin "2") (pinfunction "2_2") (pintype "unspecified"))
    )
    (net (code "154") (name "Net-(SW50-Pad6)") (class "Default")
      (node (ref "SW50") (pin "6") (pinfunction "6_6") (pintype "unspecified"))
      (node (ref "SW51") (pin "2") (pinfunction "2_2") (pintype "unspecified"))
    )
    (net (code "155") (name "Net-(SW52-Pad6)") (class "Default")
      (node (ref "SW52") (pin "6") (pinfunction "6_6") (pintype "unspecified"))
      (node (ref "SW54") (pin "2") (pinfunction "2_2") (pintype "unspecified"))
    )
    (net (code "156") (name "Net-(SW53-Pad2)") (class "Default")
      (node (ref "SW53") (pin "2") (pinfunction "2_2") (pintype "unspecified"))
      (node (ref "SW54") (pin "6") (pinfunction "6_6") (pintype "unspecified"))
    )
    (net (code "157") (name "Net-(SW53-Pad6)") (class "Default")
      (node (ref "SW53") (pin "6") (pinfunction "6_6") (pintype "unspecified"))
      (node (ref "SW56") (pin "2") (pinfunction "2_2") (pintype "unspecified"))
    )
    (net (code "158") (name "Net-(SW55-Pad2)") (class "Default")
      (node (ref "SW55") (pin "2") (pinfunction "2_2") (pintype "unspecified"))
      (node (ref "SW56") (pin "6") (pinfunction "6_6") (pintype "unspecified"))
    )
    (net (code "159") (name "Net-(SW55-Pad6)") (class "Default")
      (node (ref "SW55") (pin "6") (pinfunction "6_6") (pintype "unspecified"))
      (node (ref "SW58") (pin "2") (pinfunction "2_2") (pintype "unspecified"))
    )
    (net (code "160") (name "Net-(SW57-Pad2)") (class "Default")
      (node (ref "SW57") (pin "2") (pinfunction "2_2") (pintype "unspecified"))
      (node (ref "SW58") (pin "6") (pinfunction "6_6") (pintype "unspecified"))
    )
    (net (code "161") (name "Net-(SW57-Pad6)") (class "Default")
      (node (ref "SW57") (pin "6") (pinfunction "6_6") (pintype "unspecified"))
      (node (ref "SW60") (pin "2") (pinfunction "2_2") (pintype "unspecified"))
    )
    (net (code "162") (name "Net-(SW59-Pad2)") (class "Default")
      (node (ref "SW59") (pin "2") (pinfunction "2_2") (pintype "unspecified"))
      (node (ref "SW60") (pin "6") (pinfunction "6_6") (pintype "unspecified"))
    )
    (net (code "163") (name "Net-(SW59-Pad6)") (class "Default")
      (node (ref "SW59") (pin "6") (pinfunction "6_6") (pintype "unspecified"))
      (node (ref "SW62") (pin "2") (pinfunction "2_2") (pintype "unspecified"))
    )
    (net (code "164") (name "Net-(SW61-Pad2)") (class "Default")
      (node (ref "SW61") (pin "2") (pinfunction "2_2") (pintype "unspecified"))
      (node (ref "SW62") (pin "6") (pinfunction "6_6") (pintype "unspecified"))
    )
    (net (code "165") (name "Net-(SW61-Pad6)") (class "Default")
      (node (ref "SW61") (pin "6") (pinfunction "6_6") (pintype "unspecified"))
      (node (ref "SW63") (pin "2") (pinfunction "2_2") (pintype "unspecified"))
    )
    (net (code "166") (name "Net-(SW63-Pad6)") (class "Default")
      (node (ref "SW63") (pin "6") (pinfunction "6_6") (pintype "unspecified"))
      (node (ref "SW64") (pin "2") (pinfunction "2_2") (pintype "unspecified"))
    )
    (net (code "167") (name "Net-(SW65-Pad6)") (class "Default")
      (node (ref "SW65") (pin "6") (pinfunction "6_6") (pintype "unspecified"))
      (node (ref "SW67") (pin "2") (pinfunction "2_2") (pintype "unspecified"))
    )
    (net (code "168") (name "Net-(SW66-Pad2)") (class "Default")
      (node (ref "SW66") (pin "2") (pinfunction "2_2") (pintype "unspecified"))
      (node (ref "SW67") (pin "6") (pinfunction "6_6") (pintype "unspecified"))
    )
    (net (code "169") (name "Net-(SW66-Pad6)") (class "Default")
      (node (ref "SW66") (pin "6") (pinfunction "6_6") (pintype "unspecified"))
      (node (ref "SW69") (pin "2") (pinfunction "2_2") (pintype "unspecified"))
    )
    (net (code "170") (name "Net-(SW68-Pad2)") (class "Default")
      (node (ref "SW68") (pin "2") (pinfunction "2_2") (pintype "unspecified"))
      (node (ref "SW69") (pin "6") (pinfunction "6_6") (pintype "unspecified"))
    )
    (net (code "171") (name "Net-(SW68-Pad6)") (class "Default")
      (node (ref "SW68") (pin "6") (pinfunction "6_6") (pintype "unspecified"))
      (node (ref "SW71") (pin "2") (pinfunction "2_2") (pintype "unspecified"))
    )
    (net (code "172") (name "Net-(SW70-Pad2)") (class "Default")
      (node (ref "SW70") (pin "2") (pinfunction "2_2") (pintype "unspecified"))
      (node (ref "SW71") (pin "6") (pinfunction "6_6") (pintype "unspecified"))
    )
    (net (code "173") (name "Net-(SW70-Pad6)") (class "Default")
      (node (ref "SW70") (pin "6") (pinfunction "6_6") (pintype "unspecified"))
      (node (ref "SW73") (pin "2") (pinfunction "2_2") (pintype "unspecified"))
    )
    (net (code "174") (name "Net-(SW72-Pad2)") (class "Default")
      (node (ref "SW72") (pin "2") (pinfunction "2_2") (pintype "unspecified"))
      (node (ref "SW73") (pin "6") (pinfunction "6_6") (pintype "unspecified"))
    )
    (net (code "175") (name "Net-(SW72-Pad6)") (class "Default")
      (node (ref "SW72") (pin "6") (pinfunction "6_6") (pintype "unspecified"))
      (node (ref "SW75") (pin "2") (pinfunction "2_2") (pintype "unspecified"))
    )
    (net (code "176") (name "Net-(SW74-Pad2)") (class "Default")
      (node (ref "SW74") (pin "2") (pinfunction "2_2") (pintype "unspecified"))
      (node (ref "SW75") (pin "6") (pinfunction "6_6") (pintype "unspecified"))
    )
    (net (code "177") (name "Net-(SW74-Pad6)") (class "Default")
      (node (ref "SW74") (pin "6") (pinfunction "6_6") (pintype "unspecified"))
      (node (ref "SW76") (pin "2") (pinfunction "2_2") (pintype "unspecified"))
    )
    (net (code "178") (name "Net-(SW76-Pad6)") (class "Default")
      (node (ref "SW76") (pin "6") (pinfunction "6_6") (pintype "unspecified"))
      (node (ref "SW77") (pin "2") (pinfunction "2_2") (pintype "unspecified"))
    )
    (net (code "179") (name "Net-(SW78-Pad2)") (class "Default")
      (node (ref "SW78") (pin "2") (pinfunction "2_2") (pintype "unspecified"))
      (node (ref "SW79") (pin "6") (pinfunction "6_6") (pintype "unspecified"))
    )
    (net (code "180") (name "Net-(SW79-Pad2)") (class "Default")
      (node (ref "SW79") (pin "2") (pinfunction "2_2") (pintype "unspecified"))
      (node (ref "SW81") (pin "6") (pinfunction "6_6") (pintype "unspecified"))
    )
    (net (code "181") (name "Net-(SW80-Pad2)") (class "Default")
      (node (ref "SW80") (pin "2") (pinfunction "2_2") (pintype "unspecified"))
      (node (ref "SW83") (pin "6") (pinfunction "6_6") (pintype "unspecified"))
    )
    (net (code "182") (name "Net-(SW80-Pad6)") (class "Default")
      (node (ref "SW80") (pin "6") (pinfunction "6_6") (pintype "unspecified"))
      (node (ref "SW81") (pin "2") (pinfunction "2_2") (pintype "unspecified"))
    )
    (net (code "183") (name "Net-(SW82-Pad2)") (class "Default")
      (node (ref "SW82") (pin "2") (pinfunction "2_2") (pintype "unspecified"))
      (node (ref "SW85") (pin "6") (pinfunction "6_6") (pintype "unspecified"))
    )
    (net (code "184") (name "Net-(SW82-Pad6)") (class "Default")
      (node (ref "SW82") (pin "6") (pinfunction "6_6") (pintype "unspecified"))
      (node (ref "SW83") (pin "2") (pinfunction "2_2") (pintype "unspecified"))
    )
    (net (code "185") (name "Net-(SW84-Pad2)") (class "Default")
      (node (ref "SW84") (pin "2") (pinfunction "2_2") (pintype "unspecified"))
      (node (ref "SW87") (pin "6") (pinfunction "6_6") (pintype "unspecified"))
    )
    (net (code "186") (name "Net-(SW84-Pad6)") (class "Default")
      (node (ref "SW84") (pin "6") (pinfunction "6_6") (pintype "unspecified"))
      (node (ref "SW85") (pin "2") (pinfunction "2_2") (pintype "unspecified"))
    )
    (net (code "187") (name "Net-(SW86-Pad2)") (class "Default")
      (node (ref "SW86") (pin "2") (pinfunction "2_2") (pintype "unspecified"))
      (node (ref "SW88") (pin "6") (pinfunction "6_6") (pintype "unspecified"))
    )
    (net (code "188") (name "Net-(SW86-Pad6)") (class "Default")
      (node (ref "SW86") (pin "6") (pinfunction "6_6") (pintype "unspecified"))
      (node (ref "SW87") (pin "2") (pinfunction "2_2") (pintype "unspecified"))
    )
    (net (code "189") (name "Net-(U1-PE2(HWB#))") (class "Default")
      (node (ref "R1") (pin "1") (pinfunction "1_1") (pintype "input"))
      (node (ref "U1") (pin "33") (pinfunction "PE2(HWB#)_33") (pintype "unspecified"))
    )
    (net (code "190") (name "Net-(U1-RESET#)") (class "Default")
      (node (ref "R2") (pin "2") (pinfunction "2_2") (pintype "input"))
      (node (ref "SW1") (pin "2") (pinfunction "2_2") (pintype "unspecified"))
      (node (ref "U1") (pin "13") (pinfunction "RESET#_13") (pintype "unspecified"))
    )
    (net (code "191") (name "Net-(U1-UCap)") (class "Default")
      (node (ref "C1") (pin "1") (pinfunction "1_1") (pintype "unspecified"))
      (node (ref "U1") (pin "6") (pinfunction "UCap_6") (pintype "unspecified"))
    )
    (net (code "192") (name "Net-(U1-XTAL1)") (class "Default")
      (node (ref "C2") (pin "2") (pinfunction "2_2") (pintype "unspecified"))
      (node (ref "U1") (pin "17") (pinfunction "XTAL1_17") (pintype "unspecified"))
      (node (ref "X1") (pin "2") (pinfunction "OSC2_2") (pintype "input"))
    )
    (net (code "193") (name "Net-(U1-XTAL2)") (class "Default")
      (node (ref "C3") (pin "2") (pinfunction "2_2") (pintype "unspecified"))
      (node (ref "U1") (pin "16") (pinfunction "XTAL2_16") (pintype "unspecified"))
      (node (ref "X1") (pin "1") (pinfunction "OSC1_1") (pintype "input"))
    )
    (net (code "194") (name "Net-(U2-b)") (class "Default")
      (node (ref "SW88") (pin "2") (pinfunction "2_2") (pintype "unspecified"))
      (node (ref "U2") (pin "b5") (pinfunction "b_b5") (pintype "unspecified"))
    )
    (net (code "195") (name "Net-(USBC1-DN1)") (class "Default")
      (node (ref "R3") (pin "2") (pinfunction "2_2") (pintype "unspecified"))
      (node (ref "USBC1") (pin "A7") (pinfunction "DN1_A7") (pintype "unspecified"))
      (node (ref "USBC1") (pin "B7") (pinfunction "DN2_B7") (pintype "unspecified"))
    )
    (net (code "196") (name "Net-(USBC1-DP1)") (class "Default")
      (node (ref "R4") (pin "1") (pinfunction "1_1") (pintype "unspecified"))
      (node (ref "USBC1") (pin "A6") (pinfunction "DP1_A6") (pintype "unspecified"))
      (node (ref "USBC1") (pin "B6") (pinfunction "DP2_B6") (pintype "unspecified"))
    )
    (net (code "197") (name "RGB") (class "Default")
      (node (ref "SW2") (pin "6") (pinfunction "6_6") (pintype "unspecified"))
    )
    (net (code "198") (name "RGB1") (class "Default")
      (node (ref "SW16") (pin "2") (pinfunction "2_2") (pintype "unspecified"))
      (node (ref "SW34") (pin "6") (pinfunction "6_6") (pintype "unspecified"))
    )
    (net (code "199") (name "RGB2") (class "Default")
      (node (ref "SW19") (pin "2") (pinfunction "2_2") (pintype "unspecified"))
      (node (ref "SW35") (pin "6") (pinfunction "6_6") (pintype "unspecified"))
    )
    (net (code "200") (name "RGB3") (class "Default")
      (node (ref "SW50") (pin "2") (pinfunction "2_2") (pintype "unspecified"))
      (node (ref "SW64") (pin "6") (pinfunction "6_6") (pintype "unspecified"))
    )
    (net (code "201") (name "RGB4") (class "Default")
      (node (ref "SW52") (pin "2") (pinfunction "2_2") (pintype "unspecified"))
      (node (ref "SW77") (pin "6") (pinfunction "6_6") (pintype "unspecified"))
    )
    (net (code "202") (name "RGB5") (class "Default")
      (node (ref "SW65") (pin "2") (pinfunction "2_2") (pintype "unspecified"))
      (node (ref "SW78") (pin "6") (pinfunction "6_6") (pintype "unspecified"))
    )
    (net (code "203") (name "ROW0") (class "Default")
      (node (ref "D1") (pin "1") (pinfunction "K_1") (pintype "unspecified"))
      (node (ref "D10") (pin "1") (pinfunction "K_1") (pintype "unspecified"))
      (node (ref "D11") (pin "1") (pinfunction "K_1") (pintype "unspecified"))
      (node (ref "D12") (pin "1") (pinfunction "K_1") (pintype "unspecified"))
      (node (ref "D13") (pin "1") (pinfunction "K_1") (pintype "unspecified"))
      (node (ref "D14") (pin "1") (pinfunction "K_1") (pintype "unspecified"))
      (node (ref "D15") (pin "1") (pinfunction "K_1") (pintype "unspecified"))
      (node (ref "D16") (pin "1") (pinfunction "K_1") (pintype "unspecified"))
      (node (ref "D2") (pin "1") (pinfunction "K_1") (pintype "unspecified"))
      (node (ref "D3") (pin "1") (pinfunction "K_1") (pintype "unspecified"))
      (node (ref "D4") (pin "1") (pinfunction "K_1") (pintype "unspecified"))
      (node (ref "D5") (pin "1") (pinfunction "K_1") (pintype "unspecified"))
      (node (ref "D6") (pin "1") (pinfunction "K_1") (pintype "unspecified"))
      (node (ref "D7") (pin "1") (pinfunction "K_1") (pintype "unspecified"))
      (node (ref "D8") (pin "1") (pinfunction "K_1") (pintype "unspecified"))
      (node (ref "D9") (pin "1") (pinfunction "K_1") (pintype "unspecified"))
    )
    (net (code "204") (name "ROW1") (class "Default")
      (node (ref "D17") (pin "1") (pinfunction "K_1") (pintype "unspecified"))
      (node (ref "D18") (pin "1") (pinfunction "K_1") (pintype "unspecified"))
      (node (ref "D19") (pin "1") (pinfunction "K_1") (pintype "unspecified"))
      (node (ref "D20") (pin "1") (pinfunction "K_1") (pintype "unspecified"))
      (node (ref "D21") (pin "1") (pinfunction "K_1") (pintype "unspecified"))
      (node (ref "D22") (pin "1") (pinfunction "K_1") (pintype "unspecified"))
      (node (ref "D23") (pin "1") (pinfunction "K_1") (pintype "unspecified"))
      (node (ref "D24") (pin "1") (pinfunction "K_1") (pintype "unspecified"))
      (node (ref "D25") (pin "1") (pinfunction "K_1") (pintype "unspecified"))
      (node (ref "D26") (pin "1") (pinfunction "K_1") (pintype "unspecified"))
      (node (ref "D27") (pin "1") (pinfunction "K_1") (pintype "unspecified"))
      (node (ref "D28") (pin "1") (pinfunction "K_1") (pintype "unspecified"))
      (node (ref "D29") (pin "1") (pinfunction "K_1") (pintype "unspecified"))
      (node (ref "D30") (pin "1") (pinfunction "K_1") (pintype "unspecified"))
      (node (ref "D31") (pin "1") (pinfunction "K_1") (pintype "unspecified"))
      (node (ref "D32") (pin "1") (pinfunction "K_1") (pintype "unspecified"))
      (node (ref "D33") (pin "1") (pinfunction "K_1") (pintype "unspecified"))
    )
    (net (code "205") (name "ROW2") (class "Default")
      (node (ref "D34") (pin "1") (pinfunction "K_1") (pintype "unspecified"))
      (node (ref "D35") (pin "1") (pinfunction "K_1") (pintype "unspecified"))
      (node (ref "D36") (pin "1") (pinfunction "K_1") (pintype "unspecified"))
      (node (ref "D37") (pin "1") (pinfunction "K_1") (pintype "unspecified"))
      (node (ref "D38") (pin "1") (pinfunction "K_1") (pintype "unspecified"))
      (node (ref "D39") (pin "1") (pinfunction "K_1") (pintype "unspecified"))
      (node (ref "D40") (pin "1") (pinfunction "K_1") (pintype "unspecified"))
      (node (ref "D41") (pin "1") (pinfunction "K_1") (pintype "unspecified"))
      (node (ref "D42") (pin "1") (pinfunction "K_1") (pintype "unspecified"))
      (node (ref "D43") (pin "1") (pinfunction "K_1") (pintype "unspecified"))
      (node (ref "D44") (pin "1") (pinfunction "K_1") (pintype "unspecified"))
      (node (ref "D45") (pin "1") (pinfunction "K_1") (pintype "unspecified"))
      (node (ref "D46") (pin "1") (pinfunction "K_1") (pintype "unspecified"))
      (node (ref "D47") (pin "1") (pinfunction "K_1") (pintype "unspecified"))
      (node (ref "D48") (pin "1") (pinfunction "K_1") (pintype "unspecified"))
      (node (ref "D49") (pin "1") (pinfunction "K_1") (pintype "unspecified"))
      (node (ref "D50") (pin "1") (pinfunction "K_1") (pintype "unspecified"))
    )
    (net (code "206") (name "ROW3") (class "Default")
      (node (ref "D51") (pin "1") (pinfunction "K_1") (pintype "unspecified"))
      (node (ref "D52") (pin "1") (pinfunction "K_1") (pintype "unspecified"))
      (node (ref "D53") (pin "1") (pinfunction "K_1") (pintype "unspecified"))
      (node (ref "D54") (pin "1") (pinfunction "K_1") (pintype "unspecified"))
      (node (ref "D55") (pin "1") (pinfunction "K_1") (pintype "unspecified"))
      (node (ref "D56") (pin "1") (pinfunction "K_1") (pintype "unspecified"))
      (node (ref "D57") (pin "1") (pinfunction "K_1") (pintype "unspecified"))
      (node (ref "D58") (pin "1") (pinfunction "K_1") (pintype "unspecified"))
      (node (ref "D59") (pin "1") (pinfunction "K_1") (pintype "unspecified"))
      (node (ref "D60") (pin "1") (pinfunction "K_1") (pintype "unspecified"))
      (node (ref "D61") (pin "1") (pinfunction "K_1") (pintype "unspecified"))
      (node (ref "D62") (pin "1") (pinfunction "K_1") (pintype "unspecified"))
      (node (ref "D63") (pin "1") (pinfunction "K_1") (pintype "unspecified"))
    )
    (net (code "207") (name "ROW4") (class "Default")
      (node (ref "D64") (pin "1") (pinfunction "K_1") (pintype "unspecified"))
      (node (ref "D65") (pin "1") (pinfunction "K_1") (pintype "unspecified"))
      (node (ref "D66") (pin "1") (pinfunction "K_1") (pintype "unspecified"))
      (node (ref "D67") (pin "1") (pinfunction "K_1") (pintype "unspecified"))
      (node (ref "D68") (pin "1") (pinfunction "K_1") (pintype "unspecified"))
      (node (ref "D69") (pin "1") (pinfunction "K_1") (pintype "unspecified"))
      (node (ref "D70") (pin "1") (pinfunction "K_1") (pintype "unspecified"))
      (node (ref "D71") (pin "1") (pinfunction "K_1") (pintype "unspecified"))
      (node (ref "D72") (pin "1") (pinfunction "K_1") (pintype "unspecified"))
      (node (ref "D73") (pin "1") (pinfunction "K_1") (pintype "unspecified"))
      (node (ref "D74") (pin "1") (pinfunction "K_1") (pintype "unspecified"))
      (node (ref "D75") (pin "1") (pinfunction "K_1") (pintype "unspecified"))
      (node (ref "D76") (pin "1") (pinfunction "K_1") (pintype "unspecified"))
    )
    (net (code "208") (name "ROW5") (class "Default")
      (node (ref "D77") (pin "1") (pinfunction "K_1") (pintype "unspecified"))
      (node (ref "D78") (pin "1") (pinfunction "K_1") (pintype "unspecified"))
      (node (ref "D79") (pin "1") (pinfunction "K_1") (pintype "unspecified"))
      (node (ref "D80") (pin "1") (pinfunction "K_1") (pintype "unspecified"))
      (node (ref "D81") (pin "1") (pinfunction "K_1") (pintype "unspecified"))
      (node (ref "D82") (pin "1") (pinfunction "K_1") (pintype "unspecified"))
      (node (ref "D83") (pin "1") (pinfunction "K_1") (pintype "unspecified"))
      (node (ref "D84") (pin "1") (pinfunction "K_1") (pintype "unspecified"))
      (node (ref "D85") (pin "1") (pinfunction "K_1") (pintype "unspecified"))
      (node (ref "D86") (pin "1") (pinfunction "K_1") (pintype "unspecified"))
      (node (ref "D87") (pin "1") (pinfunction "K_1") (pintype "unspecified"))
    )
    (net (code "209") (name "VCC") (class "Default")
      (node (ref "C10") (pin "1") (pinfunction "1_1") (pintype "unspecified"))
      (node (ref "C11") (pin "1") (pinfunction "1_1") (pintype "unspecified"))
      (node (ref "C12") (pin "1") (pinfunction "1_1") (pintype "unspecified"))
      (node (ref "C13") (pin "1") (pinfunction "1_1") (pintype "unspecified"))
      (node (ref "C14") (pin "1") (pinfunction "1_1") (pintype "unspecified"))
      (node (ref "C15") (pin "1") (pinfunction "1_1") (pintype "unspecified"))
      (node (ref "C16") (pin "1") (pinfunction "1_1") (pintype "unspecified"))
      (node (ref "C17") (pin "1") (pinfunction "1_1") (pintype "unspecified"))
      (node (ref "C18") (pin "1") (pinfunction "1_1") (pintype "unspecified"))
      (node (ref "C19") (pin "1") (pinfunction "1_1") (pintype "unspecified"))
      (node (ref "C20") (pin "1") (pinfunction "1_1") (pintype "unspecified"))
      (node (ref "C21") (pin "1") (pinfunction "1_1") (pintype "unspecified"))
      (node (ref "C22") (pin "1") (pinfunction "1_1") (pintype "unspecified"))
      (node (ref "C23") (pin "1") (pinfunction "1_1") (pintype "unspecified"))
      (node (ref "C24") (pin "1") (pinfunction "1_1") (pintype "unspecified"))
      (node (ref "C25") (pin "1") (pinfunction "1_1") (pintype "unspecified"))
      (node (ref "C26") (pin "1") (pinfunction "1_1") (pintype "unspecified"))
      (node (ref "C27") (pin "1") (pinfunction "1_1") (pintype "unspecified"))
      (node (ref "C28") (pin "1") (pinfunction "1_1") (pintype "unspecified"))
      (node (ref "C29") (pin "1") (pinfunction "1_1") (pintype "unspecified"))
      (node (ref "C30") (pin "1") (pinfunction "1_1") (pintype "unspecified"))
      (node (ref "C31") (pin "1") (pinfunction "1_1") (pintype "unspecified"))
      (node (ref "C32") (pin "1") (pinfunction "1_1") (pintype "unspecified"))
      (node (ref "C33") (pin "1") (pinfunction "1_1") (pintype "unspecified"))
      (node (ref "C34") (pin "1") (pinfunction "1_1") (pintype "unspecified"))
      (node (ref "C35") (pin "1") (pinfunction "1_1") (pintype "unspecified"))
      (node (ref "C36") (pin "1") (pinfunction "1_1") (pintype "unspecified"))
      (node (ref "C37") (pin "1") (pinfunction "1_1") (pintype "unspecified"))
      (node (ref "C38") (pin "1") (pinfunction "1_1") (pintype "unspecified"))
      (node (ref "C39") (pin "1") (pinfunction "1_1") (pintype "unspecified"))
      (node (ref "C4") (pin "2") (pinfunction "2_2") (pintype "unspecified"))
      (node (ref "C40") (pin "1") (pinfunction "1_1") (pintype "unspecified"))
      (node (ref "C41") (pin "1") (pinfunction "1_1") (pintype "unspecified"))
      (node (ref "C42") (pin "1") (pinfunction "1_1") (pintype "unspecified"))
      (node (ref "C43") (pin "1") (pinfunction "1_1") (pintype "unspecified"))
      (node (ref "C44") (pin "1") (pinfunction "1_1") (pintype "unspecified"))
      (node (ref "C45") (pin "1") (pinfunction "1_1") (pintype "unspecified"))
      (node (ref "C46") (pin "1") (pinfunction "1_1") (pintype "unspecified"))
      (node (ref "C47") (pin "1") (pinfunction "1_1") (pintype "unspecified"))
      (node (ref "C48") (pin "1") (pinfunction "1_1") (pintype "unspecified"))
      (node (ref "C49") (pin "1") (pinfunction "1_1") (pintype "unspecified"))
      (node (ref "C5") (pin "2") (pinfunction "2_2") (pintype "unspecified"))
      (node (ref "C50") (pin "1") (pinfunction "1_1") (pintype "unspecified"))
      (node (ref "C51") (pin "1") (pinfunction "1_1") (pintype "unspecified"))
      (node (ref "C52") (pin "1") (pinfunction "1_1") (pintype "unspecified"))
      (node (ref "C53") (pin "1") (pinfunction "1_1") (pintype "unspecified"))
      (node (ref "C54") (pin "1") (pinfunction "1_1") (pintype "unspecified"))
      (node (ref "C55") (pin "1") (pinfunction "1_1") (pintype "unspecified"))
      (node (ref "C56") (pin "1") (pinfunction "1_1") (pintype "unspecified"))
      (node (ref "C57") (pin "1") (pinfunction "1_1") (pintype "unspecified"))
      (node (ref "C58") (pin "1") (pinfunction "1_1") (pintype "unspecified"))
      (node (ref "C59") (pin "1") (pinfunction "1_1") (pintype "unspecified"))
      (node (ref "C6") (pin "2") (pinfunction "2_2") (pintype "unspecified"))
      (node (ref "C60") (pin "1") (pinfunction "1_1") (pintype "unspecified"))
      (node (ref "C61") (pin "1") (pinfunction "1_1") (pintype "unspecified"))
      (node (ref "C62") (pin "1") (pinfunction "1_1") (pintype "unspecified"))
      (node (ref "C63") (pin "1") (pinfunction "1_1") (pintype "unspecified"))
      (node (ref "C64") (pin "1") (pinfunction "1_1") (pintype "unspecified"))
      (node (ref "C65") (pin "1") (pinfunction "1_1") (pintype "unspecified"))
      (node (ref "C66") (pin "1") (pinfunction "1_1") (pintype "unspecified"))
      (node (ref "C67") (pin "1") (pinfunction "1_1") (pintype "unspecified"))
      (node (ref "C68") (pin "1") (pinfunction "1_1") (pintype "unspecified"))
      (node (ref "C69") (pin "1") (pinfunction "1_1") (pintype "unspecified"))
      (node (ref "C7") (pin "2") (pinfunction "2_2") (pintype "unspecified"))
      (node (ref "C70") (pin "1") (pinfunction "1_1") (pintype "unspecified"))
      (node (ref "C71") (pin "1") (pinfunction "1_1") (pintype "unspecified"))
      (node (ref "C72") (pin "1") (pinfunction "1_1") (pintype "unspecified"))
      (node (ref "C73") (pin "1") (pinfunction "1_1") (pintype "unspecified"))
      (node (ref "C74") (pin "1") (pinfunction "1_1") (pintype "unspecified"))
      (node (ref "C75") (pin "1") (pinfunction "1_1") (pintype "unspecified"))
      (node (ref "C76") (pin "1") (pinfunction "1_1") (pintype "unspecified"))
      (node (ref "C77") (pin "1") (pinfunction "1_1") (pintype "unspecified"))
      (node (ref "C78") (pin "1") (pinfunction "1_1") (pintype "unspecified"))
      (node (ref "C79") (pin "1") (pinfunction "1_1") (pintype "unspecified"))
      (node (ref "C8") (pin "2") (pinfunction "2_2") (pintype "unspecified"))
      (node (ref "C80") (pin "1") (pinfunction "1_1") (pintype "unspecified"))
      (node (ref "C81") (pin "1") (pinfunction "1_1") (pintype "unspecified"))
      (node (ref "C82") (pin "1") (pinfunction "1_1") (pintype "unspecified"))
      (node (ref "C83") (pin "1") (pinfunction "1_1") (pintype "unspecified"))
      (node (ref "C84") (pin "1") (pinfunction "1_1") (pintype "unspecified"))
      (node (ref "C85") (pin "1") (pinfunction "1_1") (pintype "unspecified"))
      (node (ref "C86") (pin "1") (pinfunction "1_1") (pintype "unspecified"))
      (node (ref "C87") (pin "1") (pinfunction "1_1") (pintype "unspecified"))
      (node (ref "C88") (pin "1") (pinfunction "1_1") (pintype "unspecified"))
      (node (ref "C89") (pin "1") (pinfunction "1_1") (pintype "unspecified"))
      (node (ref "C9") (pin "1") (pinfunction "1_1") (pintype "unspecified"))
      (node (ref "C90") (pin "1") (pinfunction "1_1") (pintype "unspecified"))
      (node (ref "C91") (pin "1") (pinfunction "1_1") (pintype "unspecified"))
      (node (ref "C92") (pin "1") (pinfunction "1_1") (pintype "unspecified"))
      (node (ref "C93") (pin "1") (pinfunction "1_1") (pintype "unspecified"))
      (node (ref "C94") (pin "1") (pinfunction "1_1") (pintype "unspecified"))
      (node (ref "C96") (pin "1") (pinfunction "1_1") (pintype "unspecified"))
      (node (ref "R2") (pin "1") (pinfunction "1_1") (pintype "input"))
      (node (ref "SW10") (pin "1") (pinfunction "1_1") (pintype "unspecified"))
      (node (ref "SW11") (pin "1") (pinfunction "1_1") (pintype "unspecified"))
      (node (ref "SW12") (pin "1") (pinfunction "1_1") (pintype "unspecified"))
      (node (ref "SW13") (pin "1") (pinfunction "1_1") (pintype "unspecified"))
      (node (ref "SW14") (pin "1") (pinfunction "1_1") (pintype "unspecified"))
      (node (ref "SW15") (pin "1") (pinfunction "1_1") (pintype "unspecified"))
      (node (ref "SW16") (pin "1") (pinfunction "1_1") (pintype "unspecified"))
      (node (ref "SW17") (pin "1") (pinfunction "1_1") (pintype "unspecified"))
      (node (ref "SW18") (pin "1") (pinfunction "1_1") (pintype "unspecified"))
      (node (ref "SW19") (pin "1") (pinfunction "1_1") (pintype "unspecified"))
      (node (ref "SW2") (pin "1") (pinfunction "1_1") (pintype "unspecified"))
      (node (ref "SW20") (pin "1") (pinfunction "1_1") (pintype "unspecified"))
      (node (ref "SW21") (pin "1") (pinfunction "1_1") (pintype "unspecified"))
      (node (ref "SW22") (pin "1") (pinfunction "1_1") (pintype "unspecified"))
      (node (ref "SW23") (pin "1") (pinfunction "1_1") (pintype "unspecified"))
      (node (ref "SW24") (pin "1") (pinfunction "1_1") (pintype "unspecified"))
      (node (ref "SW25") (pin "1") (pinfunction "1_1") (pintype "unspecified"))
      (node (ref "SW26") (pin "1") (pinfunction "1_1") (pintype "unspecified"))
      (node (ref "SW27") (pin "1") (pinfunction "1_1") (pintype "unspecified"))
      (node (ref "SW28") (pin "1") (pinfunction "1_1") (pintype "unspecified"))
      (node (ref "SW29") (pin "1") (pinfunction "1_1") (pintype "unspecified"))
      (node (ref "SW3") (pin "1") (pinfunction "1_1") (pintype "unspecified"))
      (node (ref "SW30") (pin "1") (pinfunction "1_1") (pintype "unspecified"))
      (node (ref "SW31") (pin "1") (pinfunction "1_1") (pintype "unspecified"))
      (node (ref "SW32") (pin "1") (pinfunction "1_1") (pintype "unspecified"))
      (node (ref "SW33") (pin "1") (pinfunction "1_1") (pintype "unspecified"))
      (node (ref "SW34") (pin "1") (pinfunction "1_1") (pintype "unspecified"))
      (node (ref "SW35") (pin "1") (pinfunction "1_1") (pintype "unspecified"))
      (node (ref "SW36") (pin "1") (pinfunction "1_1") (pintype "unspecified"))
      (node (ref "SW37") (pin "1") (pinfunction "1_1") (pintype "unspecified"))
      (node (ref "SW38") (pin "1") (pinfunction "1_1") (pintype "unspecified"))
      (node (ref "SW39") (pin "1") (pinfunction "1_1") (pintype "unspecified"))
      (node (ref "SW4") (pin "1") (pinfunction "1_1") (pintype "unspecified"))
      (node (ref "SW40") (pin "1") (pinfunction "1_1") (pintype "unspecified"))
      (node (ref "SW41") (pin "1") (pinfunction "1_1") (pintype "unspecified"))
      (node (ref "SW42") (pin "1") (pinfunction "1_1") (pintype "unspecified"))
      (node (ref "SW43") (pin "1") (pinfunction "1_1") (pintype "unspecified"))
      (node (ref "SW44") (pin "1") (pinfunction "1_1") (pintype "unspecified"))
      (node (ref "SW45") (pin "1") (pinfunction "1_1") (pintype "unspecified"))
      (node (ref "SW46") (pin "1") (pinfunction "1_1") (pintype "unspecified"))
      (node (ref "SW47") (pin "1") (pinfunction "1_1") (pintype "unspecified"))
      (node (ref "SW48") (pin "1") (pinfunction "1_1") (pintype "unspecified"))
      (node (ref "SW49") (pin "1") (pinfunction "1_1") (pintype "unspecified"))
      (node (ref "SW5") (pin "1") (pinfunction "1_1") (pintype "unspecified"))
      (node (ref "SW50") (pin "1") (pinfunction "1_1") (pintype "unspecified"))
      (node (ref "SW51") (pin "1") (pinfunction "1_1") (pintype "unspecified"))
      (node (ref "SW52") (pin "1") (pinfunction "1_1") (pintype "unspecified"))
      (node (ref "SW53") (pin "1") (pinfunction "1_1") (pintype "unspecified"))
      (node (ref "SW54") (pin "1") (pinfunction "1_1") (pintype "unspecified"))
      (node (ref "SW55") (pin "1") (pinfunction "1_1") (pintype "unspecified"))
      (node (ref "SW56") (pin "1") (pinfunction "1_1") (pintype "unspecified"))
      (node (ref "SW57") (pin "1") (pinfunction "1_1") (pintype "unspecified"))
      (node (ref "SW58") (pin "1") (pinfunction "1_1") (pintype "unspecified"))
      (node (ref "SW59") (pin "1") (pinfunction "1_1") (pintype "unspecified"))
      (node (ref "SW6") (pin "1") (pinfunction "1_1") (pintype "unspecified"))
      (node (ref "SW60") (pin "1") (pinfunction "1_1") (pintype "unspecified"))
      (node (ref "SW61") (pin "1") (pinfunction "1_1") (pintype "unspecified"))
      (node (ref "SW62") (pin "1") (pinfunction "1_1") (pintype "unspecified"))
      (node (ref "SW63") (pin "1") (pinfunction "1_1") (pintype "unspecified"))
      (node (ref "SW64") (pin "1") (pinfunction "1_1") (pintype "unspecified"))
      (node (ref "SW65") (pin "1") (pinfunction "1_1") (pintype "unspecified"))
      (node (ref "SW66") (pin "1") (pinfunction "1_1") (pintype "unspecified"))
      (node (ref "SW67") (pin "1") (pinfunction "1_1") (pintype "unspecified"))
      (node (ref "SW68") (pin "1") (pinfunction "1_1") (pintype "unspecified"))
      (node (ref "SW69") (pin "1") (pinfunction "1_1") (pintype "unspecified"))
      (node (ref "SW7") (pin "1") (pinfunction "1_1") (pintype "unspecified"))
      (node (ref "SW70") (pin "1") (pinfunction "1_1") (pintype "unspecified"))
      (node (ref "SW71") (pin "1") (pinfunction "1_1") (pintype "unspecified"))
      (node (ref "SW72") (pin "1") (pinfunction "1_1") (pintype "unspecified"))
      (node (ref "SW73") (pin "1") (pinfunction "1_1") (pintype "unspecified"))
      (node (ref "SW74") (pin "1") (pinfunction "1_1") (pintype "unspecified"))
      (node (ref "SW75") (pin "1") (pinfunction "1_1") (pintype "unspecified"))
      (node (ref "SW76") (pin "1") (pinfunction "1_1") (pintype "unspecified"))
      (node (ref "SW77") (pin "1") (pinfunction "1_1") (pintype "unspecified"))
      (node (ref "SW78") (pin "1") (pinfunction "1_1") (pintype "unspecified"))
      (node (ref "SW79") (pin "1") (pinfunction "1_1") (pintype "unspecified"))
      (node (ref "SW8") (pin "1") (pinfunction "1_1") (pintype "unspecified"))
      (node (ref "SW80") (pin "1") (pinfunction "1_1") (pintype "unspecified"))
      (node (ref "SW81") (pin "1") (pinfunction "1_1") (pintype "unspecified"))
      (node (ref "SW82") (pin "1") (pinfunction "1_1") (pintype "unspecified"))
      (node (ref "SW83") (pin "1") (pinfunction "1_1") (pintype "unspecified"))
      (node (ref "SW84") (pin "1") (pinfunction "1_1") (pintype "unspecified"))
      (node (ref "SW85") (pin "1") (pinfunction "1_1") (pintype "unspecified"))
      (node (ref "SW86") (pin "1") (pinfunction "1_1") (pintype "unspecified"))
      (node (ref "SW87") (pin "1") (pinfunction "1_1") (pintype "unspecified"))
      (node (ref "SW88") (pin "1") (pinfunction "1_1") (pintype "unspecified"))
      (node (ref "SW9") (pin "1") (pinfunction "1_1") (pintype "unspecified"))
      (node (ref "U1") (pin "14") (pinfunction "VCC_14") (pintype "unspecified"))
      (node (ref "U1") (pin "2") (pinfunction "UVcc_2") (pintype "unspecified"))
      (node (ref "U1") (pin "24") (pinfunction "AVCC_24") (pintype "unspecified"))
      (node (ref "U1") (pin "34") (pinfunction "VCC_34") (pintype "unspecified"))
      (node (ref "U1") (pin "44") (pinfunction "AVCC_44") (pintype "unspecified"))
      (node (ref "U1") (pin "7") (pinfunction "VBus_7") (pintype "unspecified"))
      (node (ref "U2") (pin "c6") (pinfunction "c_c6") (pintype "unspecified"))
    )
    (net (code "210") (name "unconnected-(U1-AREF-Pad42)") (class "Default")
      (node (ref "U1") (pin "42") (pinfunction "AREF_42") (pintype "unspecified"))
    )
    (net (code "211") (name "unconnected-(U1-PB0(SS{slash}PCINT0)-Pad8)") (class "Default")
      (node (ref "U1") (pin "8") (pinfunction "PB0(SS/PCINT0)_8") (pintype "unspecified"))
    )
    (net (code "212") (name "unconnected-(U1-PB1(PCINT1{slash}SCLK)-Pad9)") (class "Default")
      (node (ref "U1") (pin "9") (pinfunction "PB1(PCINT1/SCLK)_9") (pintype "unspecified"))
    )
    (net (code "213") (name "unconnected-(U1-PB2(PDI{slash}PCINT2{slash}MOSI)-Pad10)") (class "Default")
      (node (ref "U1") (pin "10") (pinfunction "PB2(PDI/PCINT2/MOSI)_10") (pintype "unspecified"))
    )
    (net (code "214") (name "unconnected-(U1-PB3(PDO{slash}PCINT3{slash}MISO)-Pad11)") (class "Default")
      (node (ref "U1") (pin "11") (pinfunction "PB3(PDO/PCINT3/MISO)_11") (pintype "unspecified"))
    )
    (net (code "215") (name "unconnected-(U1-PB4(PCINT4{slash}ADC11)-Pad28)") (class "Default")
      (node (ref "U1") (pin "28") (pinfunction "PB4(PCINT4/ADC11)_28") (pintype "unspecified"))
    )
    (net (code "216") (name "unconnected-(U1-PB5(PCINT5{slash}OC1A{slash}OC4B#{slash}ADC12)-Pad29)") (class "Default")
      (node (ref "U1") (pin "29") (pinfunction "PB5(PCINT5/OC1A/OC4B#/ADC12)_29") (pintype "unspecified"))
    )
    (net (code "217") (name "unconnected-(U1-PB6(PCINT6{slash}OC1B{slash}OC4B{slash}ADC13)-Pad30)") (class "Default")
      (node (ref "U1") (pin "30") (pinfunction "PB6(PCINT6/OC1B/OC4B/ADC13)_30") (pintype "unspecified"))
    )
    (net (code "218") (name "unconnected-(U1-PB7(PCINT7{slash}OC0A{slash}OC1C{slash}RTS#)-Pad12)") (class "Default")
      (node (ref "U1") (pin "12") (pinfunction "PB7(PCINT7/OC0A/OC1C/RTS#)_12") (pintype "unspecified"))
    )
    (net (code "219") (name "unconnected-(U1-PC6(OC3A{slash}OC4A#)-Pad31)") (class "Default")
      (node (ref "U1") (pin "31") (pinfunction "PC6(OC3A/OC4A#)_31") (pintype "unspecified"))
    )
    (net (code "220") (name "unconnected-(U1-PC7(ICP3{slash}CLK0{slash}OC4A)-Pad32)") (class "Default")
      (node (ref "U1") (pin "32") (pinfunction "PC7(ICP3/CLK0/OC4A)_32") (pintype "unspecified"))
    )
    (net (code "221") (name "unconnected-(U1-PD0(OC0B{slash}SCL{slash}INT0)-Pad18)") (class "Default")
      (node (ref "U1") (pin "18") (pinfunction "PD0(OC0B/SCL/INT0)_18") (pintype "unspecified"))
    )
    (net (code "222") (name "unconnected-(U1-PD1(SDA{slash}INT1)-Pad19)") (class "Default")
      (node (ref "U1") (pin "19") (pinfunction "PD1(SDA/INT1)_19") (pintype "unspecified"))
    )
    (net (code "223") (name "unconnected-(U1-PD2(RXD1{slash}INT2)-Pad20)") (class "Default")
      (node (ref "U1") (pin "20") (pinfunction "PD2(RXD1/INT2)_20") (pintype "unspecified"))
    )
    (net (code "224") (name "unconnected-(U1-PD3(TXD1{slash}INT3)-Pad21)") (class "Default")
      (node (ref "U1") (pin "21") (pinfunction "PD3(TXD1/INT3)_21") (pintype "unspecified"))
    )
    (net (code "225") (name "unconnected-(U1-PD4(ICP1{slash}ADC8)-Pad25)") (class "Default")
      (node (ref "U1") (pin "25") (pinfunction "PD4(ICP1/ADC8)_25") (pintype "unspecified"))
    )
    (net (code "226") (name "unconnected-(U1-PD5(XCK1{slash}CTS#)-Pad22)") (class "Default")
      (node (ref "U1") (pin "22") (pinfunction "PD5(XCK1/CTS#)_22") (pintype "unspecified"))
    )
    (net (code "227") (name "unconnected-(U1-PD6(T1{slash}OC4D#{slash}ADC9)-Pad26)") (class "Default")
      (node (ref "U1") (pin "26") (pinfunction "PD6(T1/OC4D#/ADC9)_26") (pintype "unspecified"))
    )
    (net (code "228") (name "unconnected-(U1-PD7(T0{slash}OC4D{slash}ADC10)-Pad27)") (class "Default")
      (node (ref "U1") (pin "27") (pinfunction "PD7(T0/OC4D/ADC10)_27") (pintype "unspecified"))
    )
    (net (code "229") (name "unconnected-(U1-PE6(INT.6{slash}AIN0)-Pad1)") (class "Default")
      (node (ref "U1") (pin "1") (pinfunction "PE6(INT.6/AIN0)_1") (pintype "unspecified"))
    )
    (net (code "230") (name "unconnected-(U1-PF0(ADC0)-Pad41)") (class "Default")
      (node (ref "U1") (pin "41") (pinfunction "PF0(ADC0)_41") (pintype "unspecified"))
    )
    (net (code "231") (name "unconnected-(U1-PF1(ADC1)-Pad40)") (class "Default")
      (node (ref "U1") (pin "40") (pinfunction "PF1(ADC1)_40") (pintype "unspecified"))
    )
    (net (code "232") (name "unconnected-(U1-PF4(ADC4{slash}TCK)-Pad39)") (class "Default")
      (node (ref "U1") (pin "39") (pinfunction "PF4(ADC4/TCK)_39") (pintype "unspecified"))
    )
    (net (code "233") (name "unconnected-(U1-PF5(ADC5{slash}TMS)-Pad38)") (class "Default")
      (node (ref "U1") (pin "38") (pinfunction "PF5(ADC5/TMS)_38") (pintype "unspecified"))
    )
    (net (code "234") (name "unconnected-(U1-PF6(ADC6{slash}TDO)-Pad37)") (class "Default")
      (node (ref "U1") (pin "37") (pinfunction "PF6(ADC6/TDO)_37") (pintype "unspecified"))
    )
    (net (code "235") (name "unconnected-(U1-PF7(ADC7{slash}TDI)-Pad36)") (class "Default")
      (node (ref "U1") (pin "36") (pinfunction "PF7(ADC7/TDI)_36") (pintype "unspecified"))
    )
    (net (code "236") (name "unconnected-(USBC1-CC1-PadA5)") (class "Default")
      (node (ref "USBC1") (pin "A5") (pinfunction "CC1_A5") (pintype "unspecified+no_connect"))
    )
    (net (code "237") (name "unconnected-(USBC1-CC2-PadB5)") (class "Default")
      (node (ref "USBC1") (pin "B5") (pinfunction "CC2_B5") (pintype "unspecified+no_connect"))
    )
    (net (code "238") (name "unconnected-(USBC1-SBU1-PadA8)") (class "Default")
      (node (ref "USBC1") (pin "A8") (pinfunction "SBU1_A8") (pintype "unspecified+no_connect"))
    )
    (net (code "239") (name "unconnected-(USBC1-SBU2-PadB8)") (class "Default")
      (node (ref "USBC1") (pin "B8") (pinfunction "SBU2_B8") (pintype "unspecified+no_connect"))
    )
  )
)
